# homeboard15.net
KiCad netlist of a schematic drawn in EAGLE
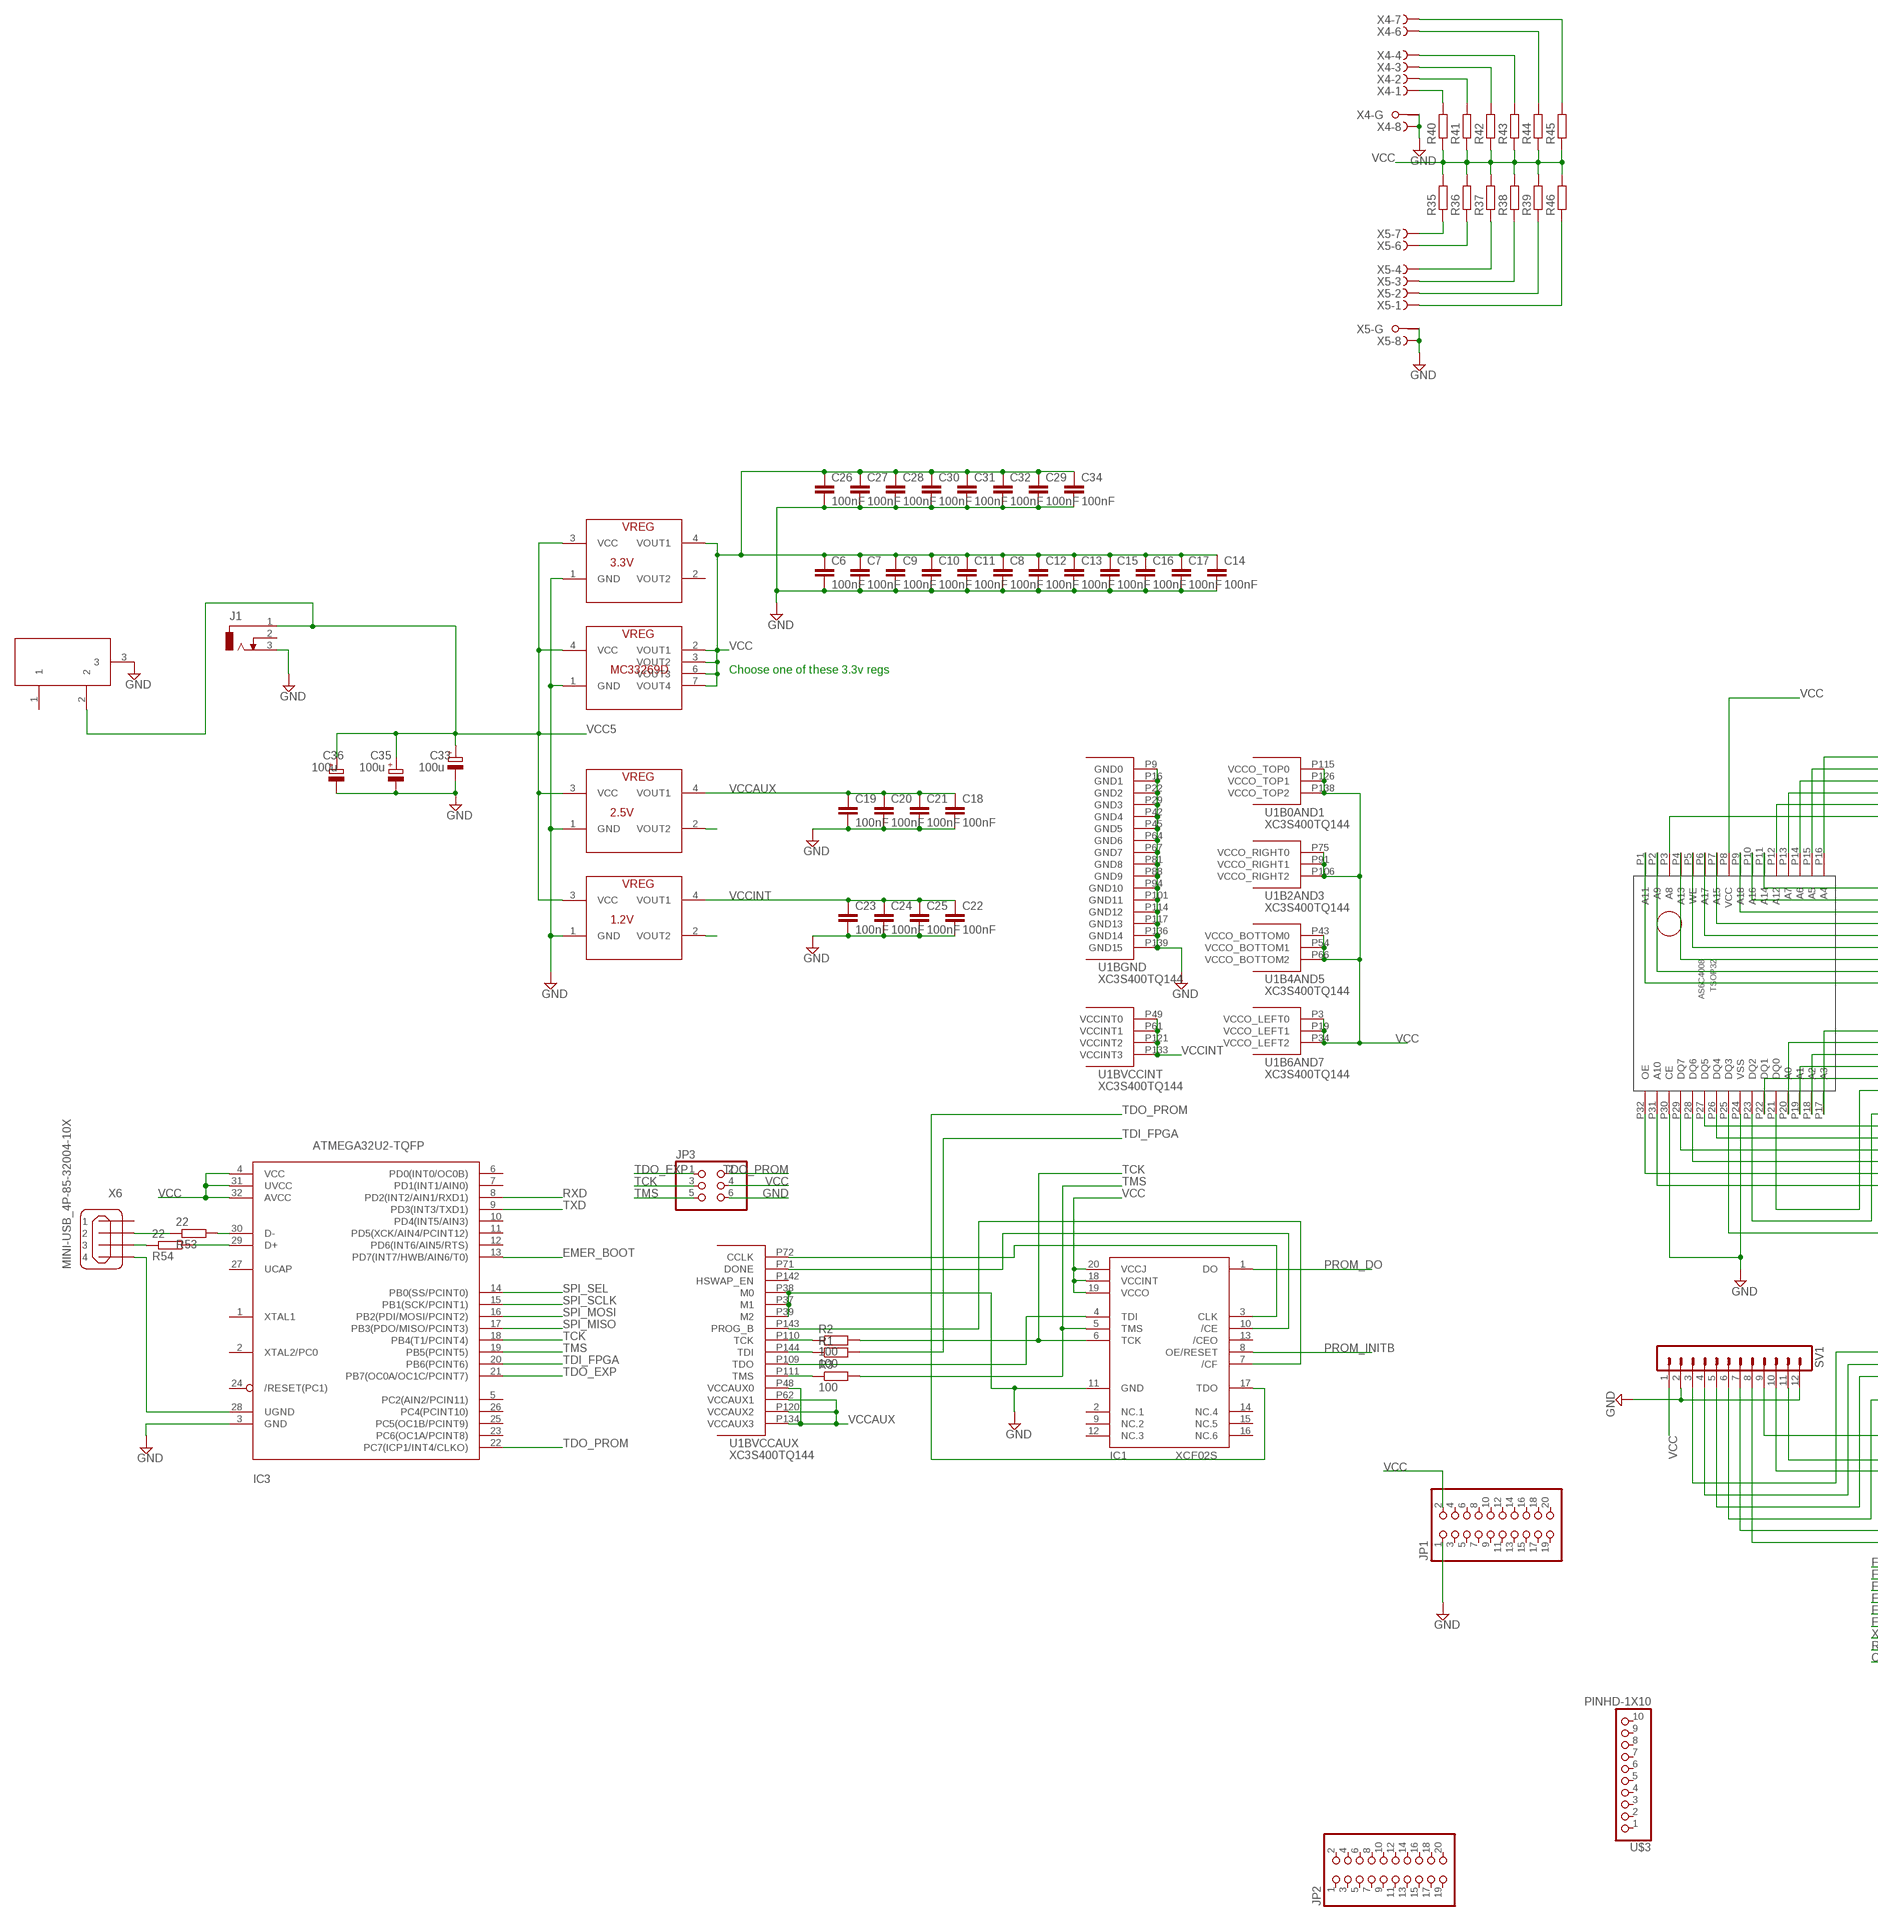
[diagram p0: schematic, sheet 1, part 1 of 3]
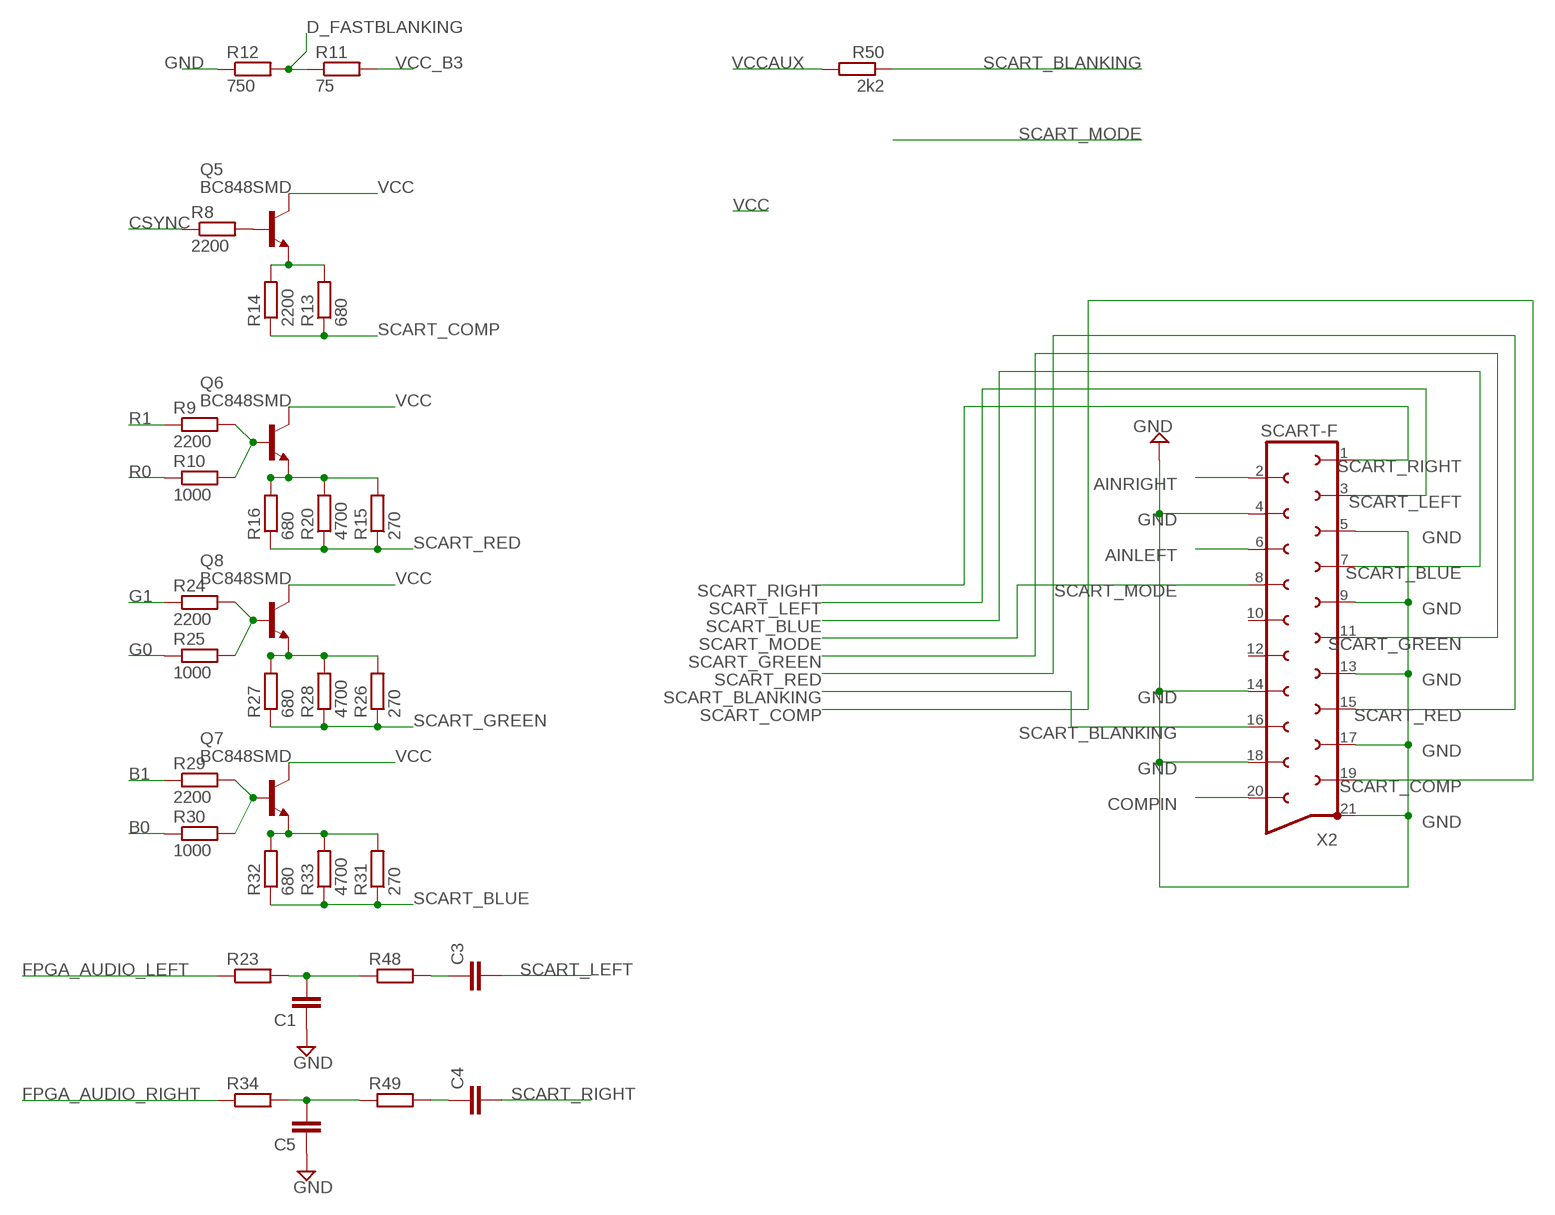
[diagram p1: schematic, sheet 1, part 2 of 3]
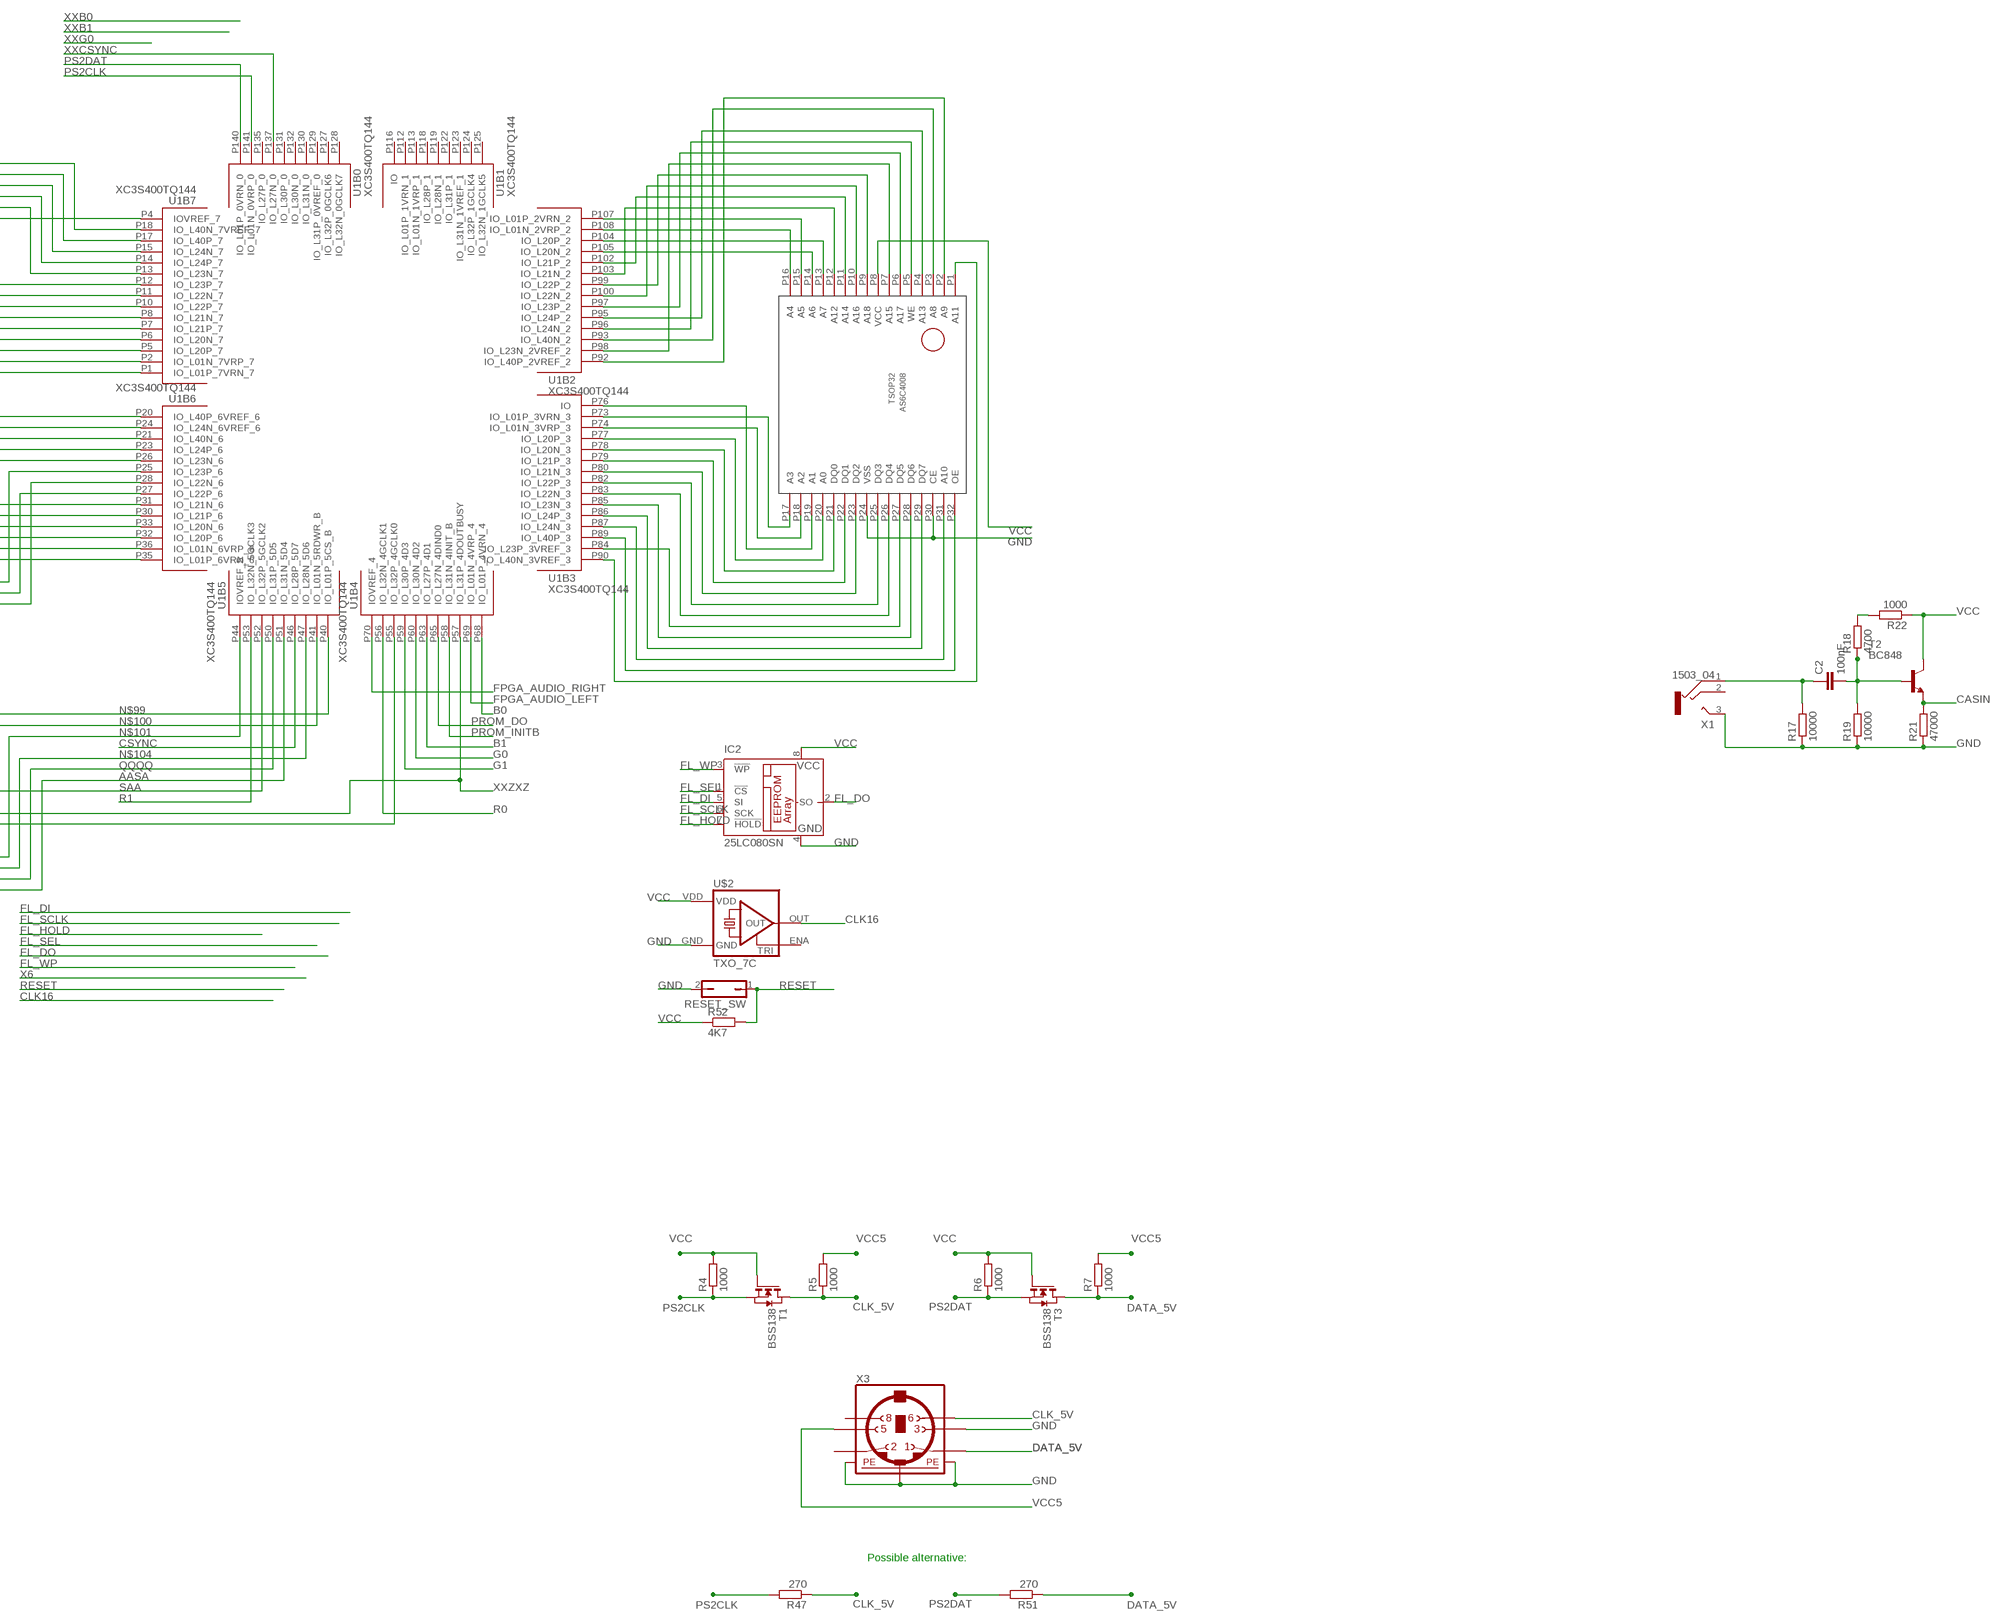
[diagram p2: schematic, sheet 1, part 3 of 3]

(export (version "E")
  (design (tool "Eeschema 10.0.6"))
  (components
    (comp (ref "C1")
      (value "C-EUC0603")
      (footprint "eagle-import:C0603")
      (libsource (lib "eagle-import") (part "resistor_C-EUC0603"))
    )
    (comp (ref "C2")
      (value "100nF")
      (footprint "eagle-import:C0603")
      (libsource (lib "eagle-import") (part "resistor_C-EUC0603"))
    )
    (comp (ref "C3")
      (value "C-EUC0603")
      (footprint "eagle-import:C0603")
      (libsource (lib "eagle-import") (part "resistor_C-EUC0603"))
    )
    (comp (ref "C4")
      (value "C-EUC0603")
      (footprint "eagle-import:C0603")
      (libsource (lib "eagle-import") (part "resistor_C-EUC0603"))
    )
    (comp (ref "C5")
      (value "C-EUC0603")
      (footprint "eagle-import:C0603")
      (libsource (lib "eagle-import") (part "resistor_C-EUC0603"))
    )
    (comp (ref "C6")
      (value "100nF")
      (footprint "eagle-import:C0603")
      (libsource (lib "eagle-import") (part "C-EUC0603"))
    )
    (comp (ref "C7")
      (value "100nF")
      (footprint "eagle-import:C0603")
      (libsource (lib "eagle-import") (part "C-EUC0603"))
    )
    (comp (ref "C8")
      (value "100nF")
      (footprint "eagle-import:C0603")
      (libsource (lib "eagle-import") (part "C-EUC0603"))
    )
    (comp (ref "C9")
      (value "100nF")
      (footprint "eagle-import:C0603")
      (libsource (lib "eagle-import") (part "C-EUC0603"))
    )
    (comp (ref "C10")
      (value "100nF")
      (footprint "eagle-import:C0603")
      (libsource (lib "eagle-import") (part "C-EUC0603"))
    )
    (comp (ref "C11")
      (value "100nF")
      (footprint "eagle-import:C0603")
      (libsource (lib "eagle-import") (part "C-EUC0603"))
    )
    (comp (ref "C12")
      (value "100nF")
      (footprint "eagle-import:C0603")
      (libsource (lib "eagle-import") (part "C-EUC0603"))
    )
    (comp (ref "C13")
      (value "100nF")
      (footprint "eagle-import:C0603")
      (libsource (lib "eagle-import") (part "C-EUC0603"))
    )
    (comp (ref "C14")
      (value "100nF")
      (footprint "eagle-import:C0603")
      (libsource (lib "eagle-import") (part "C-EUC0603"))
    )
    (comp (ref "C15")
      (value "100nF")
      (footprint "eagle-import:C0603")
      (libsource (lib "eagle-import") (part "C-EUC0603"))
    )
    (comp (ref "C16")
      (value "100nF")
      (footprint "eagle-import:C0603")
      (libsource (lib "eagle-import") (part "C-EUC0603"))
    )
    (comp (ref "C17")
      (value "100nF")
      (footprint "eagle-import:C0603")
      (libsource (lib "eagle-import") (part "C-EUC0603"))
    )
    (comp (ref "C18")
      (value "100nF")
      (footprint "eagle-import:C0603")
      (libsource (lib "eagle-import") (part "C-EUC0603"))
    )
    (comp (ref "C19")
      (value "100nF")
      (footprint "eagle-import:C0603")
      (libsource (lib "eagle-import") (part "C-EUC0603"))
    )
    (comp (ref "C20")
      (value "100nF")
      (footprint "eagle-import:C0603")
      (libsource (lib "eagle-import") (part "C-EUC0603"))
    )
    (comp (ref "C21")
      (value "100nF")
      (footprint "eagle-import:C0603")
      (libsource (lib "eagle-import") (part "C-EUC0603"))
    )
    (comp (ref "C22")
      (value "100nF")
      (footprint "eagle-import:C0603")
      (libsource (lib "eagle-import") (part "C-EUC0603"))
    )
    (comp (ref "C23")
      (value "100nF")
      (footprint "eagle-import:C0603")
      (libsource (lib "eagle-import") (part "C-EUC0603"))
    )
    (comp (ref "C24")
      (value "100nF")
      (footprint "eagle-import:C0603")
      (libsource (lib "eagle-import") (part "C-EUC0603"))
    )
    (comp (ref "C25")
      (value "100nF")
      (footprint "eagle-import:C0603")
      (libsource (lib "eagle-import") (part "C-EUC0603"))
    )
    (comp (ref "C26")
      (value "100nF")
      (footprint "eagle-import:C0603")
      (libsource (lib "eagle-import") (part "C-EUC0603"))
    )
    (comp (ref "C27")
      (value "100nF")
      (footprint "eagle-import:C0603")
      (libsource (lib "eagle-import") (part "C-EUC0603"))
    )
    (comp (ref "C28")
      (value "100nF")
      (footprint "eagle-import:C0603")
      (libsource (lib "eagle-import") (part "C-EUC0603"))
    )
    (comp (ref "C29")
      (value "100nF")
      (footprint "eagle-import:C0603")
      (libsource (lib "eagle-import") (part "C-EUC0603"))
    )
    (comp (ref "C30")
      (value "100nF")
      (footprint "eagle-import:C0603")
      (libsource (lib "eagle-import") (part "C-EUC0603"))
    )
    (comp (ref "C31")
      (value "100nF")
      (footprint "eagle-import:C0603")
      (libsource (lib "eagle-import") (part "C-EUC0603"))
    )
    (comp (ref "C32")
      (value "100nF")
      (footprint "eagle-import:C0603")
      (libsource (lib "eagle-import") (part "C-EUC0603"))
    )
    (comp (ref "C33")
      (value "100u")
      (footprint "eagle-import:PANASONIC_D")
      (libsource (lib "eagle-import") (part "CPOL-EUD"))
    )
    (comp (ref "C34")
      (value "100nF")
      (footprint "eagle-import:C0603")
      (libsource (lib "eagle-import") (part "C-EUC0603"))
    )
    (comp (ref "C35")
      (value "100u")
      (footprint "eagle-import:PANASONIC_D")
      (libsource (lib "eagle-import") (part "CPOL-EUD"))
    )
    (comp (ref "C36")
      (value "100u")
      (footprint "eagle-import:PANASONIC_D")
      (libsource (lib "eagle-import") (part "CPOL-EUD"))
    )
    (comp (ref "IC1")
      (value "XCF02S")
      (footprint "eagle-import:VO20")
      (libsource (lib "eagle-import") (part "XCF02S"))
    )
    (comp (ref "IC2")
      (value "25LC080SN")
      (footprint "eagle-import:SO-08")
      (fields (field (name "MF") "MICROCHIP") (field (name "MPN") "25LC080/SN"))
      (libsource (lib "eagle-import") (part "25SNLC080"))
    )
    (comp (ref "IC3")
      (value "ATMEGA32U2-TQFP")
      (footprint "eagle-import:TQFP32-08")
      (libsource (lib "eagle-import") (part "ATMEGA32U2-TQFP"))
    )
    (comp (ref "J1")
      (value "DCJ0303")
      (footprint "eagle-import:DCJ0303")
      (libsource (lib "eagle-import") (part "DCJ0303"))
    )
    (comp (ref "JP1")
      (value "PINHD-2X10")
      (footprint "eagle-import:2X10")
      (libsource (lib "eagle-import") (part "PINHD-2X10"))
    )
    (comp (ref "JP2")
      (value "PINHD-2X10")
      (footprint "eagle-import:2X10")
      (libsource (lib "eagle-import") (part "PINHD-2X10"))
    )
    (comp (ref "JP3")
      (value "PINHD-2X3")
      (footprint "eagle-import:2X03")
      (libsource (lib "eagle-import") (part "PINHD-2X3"))
    )
    (comp (ref "Q5")
      (value "BC848SMD")
      (footprint "eagle-import:SOT23")
      (libsource (lib "eagle-import") (part "BC848SMD"))
    )
    (comp (ref "Q6")
      (value "BC848SMD")
      (footprint "eagle-import:SOT23")
      (libsource (lib "eagle-import") (part "BC848SMD"))
    )
    (comp (ref "Q7")
      (value "BC848SMD")
      (footprint "eagle-import:SOT23")
      (libsource (lib "eagle-import") (part "BC848SMD"))
    )
    (comp (ref "Q8")
      (value "BC848SMD")
      (footprint "eagle-import:SOT23")
      (libsource (lib "eagle-import") (part "BC848SMD"))
    )
    (comp (ref "R1")
      (value "100")
      (footprint "eagle-import:R0805")
      (libsource (lib "eagle-import") (part "R-EU_R0805"))
    )
    (comp (ref "R2")
      (value "100")
      (footprint "eagle-import:R0805")
      (libsource (lib "eagle-import") (part "R-EU_R0805"))
    )
    (comp (ref "R3")
      (value "100")
      (footprint "eagle-import:R0805")
      (libsource (lib "eagle-import") (part "R-EU_R0805"))
    )
    (comp (ref "R4")
      (value "1000")
      (footprint "eagle-import:R0805")
      (libsource (lib "eagle-import") (part "R-EU_R0805"))
    )
    (comp (ref "R5")
      (value "1000")
      (footprint "eagle-import:R0805")
      (libsource (lib "eagle-import") (part "R-EU_R0805"))
    )
    (comp (ref "R6")
      (value "1000")
      (footprint "eagle-import:R0805")
      (libsource (lib "eagle-import") (part "R-EU_R0805"))
    )
    (comp (ref "R7")
      (value "1000")
      (footprint "eagle-import:R0805")
      (libsource (lib "eagle-import") (part "R-EU_R0805"))
    )
    (comp (ref "R8")
      (value "2200")
      (footprint "eagle-import:R0805")
      (libsource (lib "eagle-import") (part "R-EU_R0805"))
    )
    (comp (ref "R9")
      (value "2200")
      (footprint "eagle-import:R0805")
      (libsource (lib "eagle-import") (part "R-EU_R0805"))
    )
    (comp (ref "R10")
      (value "1000")
      (footprint "eagle-import:R0805")
      (libsource (lib "eagle-import") (part "R-EU_R0805"))
    )
    (comp (ref "R11")
      (value "75")
      (footprint "eagle-import:R0805")
      (libsource (lib "eagle-import") (part "R-EU_R0805"))
    )
    (comp (ref "R12")
      (value "750")
      (footprint "eagle-import:R0805")
      (libsource (lib "eagle-import") (part "R-EU_R0805"))
    )
    (comp (ref "R13")
      (value "680")
      (footprint "eagle-import:R0805")
      (libsource (lib "eagle-import") (part "R-EU_R0805"))
    )
    (comp (ref "R14")
      (value "2200")
      (footprint "eagle-import:R0805")
      (libsource (lib "eagle-import") (part "R-EU_R0805"))
    )
    (comp (ref "R15")
      (value "270")
      (footprint "eagle-import:R0805")
      (libsource (lib "eagle-import") (part "R-EU_R0805"))
    )
    (comp (ref "R16")
      (value "680")
      (footprint "eagle-import:R0805")
      (libsource (lib "eagle-import") (part "R-EU_R0805"))
    )
    (comp (ref "R17")
      (value "10000")
      (footprint "eagle-import:R0805")
      (libsource (lib "eagle-import") (part "R-EU_R0805"))
    )
    (comp (ref "R18")
      (value "4700")
      (footprint "eagle-import:R0805")
      (libsource (lib "eagle-import") (part "R-EU_R0805"))
    )
    (comp (ref "R19")
      (value "10000")
      (footprint "eagle-import:R0805")
      (libsource (lib "eagle-import") (part "R-EU_R0805"))
    )
    (comp (ref "R20")
      (value "4700")
      (footprint "eagle-import:R0805")
      (libsource (lib "eagle-import") (part "R-EU_R0805"))
    )
    (comp (ref "R21")
      (value "47000")
      (footprint "eagle-import:R0805")
      (libsource (lib "eagle-import") (part "R-EU_R0805"))
    )
    (comp (ref "R22")
      (value "1000")
      (footprint "eagle-import:R0805")
      (libsource (lib "eagle-import") (part "R-EU_R0805"))
    )
    (comp (ref "R23")
      (value "R-EU_M0805")
      (footprint "eagle-import:M0805")
      (libsource (lib "eagle-import") (part "resistor_R-EU_M0805"))
    )
    (comp (ref "R24")
      (value "2200")
      (footprint "eagle-import:R0805")
      (libsource (lib "eagle-import") (part "R-EU_R0805"))
    )
    (comp (ref "R25")
      (value "1000")
      (footprint "eagle-import:R0805")
      (libsource (lib "eagle-import") (part "R-EU_R0805"))
    )
    (comp (ref "R26")
      (value "270")
      (footprint "eagle-import:R0805")
      (libsource (lib "eagle-import") (part "R-EU_R0805"))
    )
    (comp (ref "R27")
      (value "680")
      (footprint "eagle-import:R0805")
      (libsource (lib "eagle-import") (part "R-EU_R0805"))
    )
    (comp (ref "R28")
      (value "4700")
      (footprint "eagle-import:R0805")
      (libsource (lib "eagle-import") (part "R-EU_R0805"))
    )
    (comp (ref "R29")
      (value "2200")
      (footprint "eagle-import:R0805")
      (libsource (lib "eagle-import") (part "R-EU_R0805"))
    )
    (comp (ref "R30")
      (value "1000")
      (footprint "eagle-import:R0805")
      (libsource (lib "eagle-import") (part "R-EU_R0805"))
    )
    (comp (ref "R31")
      (value "270")
      (footprint "eagle-import:R0805")
      (libsource (lib "eagle-import") (part "R-EU_R0805"))
    )
    (comp (ref "R32")
      (value "680")
      (footprint "eagle-import:R0805")
      (libsource (lib "eagle-import") (part "R-EU_R0805"))
    )
    (comp (ref "R33")
      (value "4700")
      (footprint "eagle-import:R0805")
      (libsource (lib "eagle-import") (part "R-EU_R0805"))
    )
    (comp (ref "R34")
      (value "R-EU_M0805")
      (footprint "eagle-import:M0805")
      (libsource (lib "eagle-import") (part "resistor_R-EU_M0805"))
    )
    (comp (ref "R35")
      (value "R-EU_M0805")
      (footprint "eagle-import:M0805")
      (libsource (lib "eagle-import") (part "resistor_R-EU_M0805"))
    )
    (comp (ref "R36")
      (value "R-EU_M0805")
      (footprint "eagle-import:M0805")
      (libsource (lib "eagle-import") (part "resistor_R-EU_M0805"))
    )
    (comp (ref "R37")
      (value "R-EU_M0805")
      (footprint "eagle-import:M0805")
      (libsource (lib "eagle-import") (part "resistor_R-EU_M0805"))
    )
    (comp (ref "R38")
      (value "R-EU_M0805")
      (footprint "eagle-import:M0805")
      (libsource (lib "eagle-import") (part "resistor_R-EU_M0805"))
    )
    (comp (ref "R39")
      (value "R-EU_M0805")
      (footprint "eagle-import:M0805")
      (libsource (lib "eagle-import") (part "resistor_R-EU_M0805"))
    )
    (comp (ref "R40")
      (value "R-EU_M0805")
      (footprint "eagle-import:M0805")
      (libsource (lib "eagle-import") (part "resistor_R-EU_M0805"))
    )
    (comp (ref "R41")
      (value "R-EU_M0805")
      (footprint "eagle-import:M0805")
      (libsource (lib "eagle-import") (part "resistor_R-EU_M0805"))
    )
    (comp (ref "R42")
      (value "R-EU_M0805")
      (footprint "eagle-import:M0805")
      (libsource (lib "eagle-import") (part "resistor_R-EU_M0805"))
    )
    (comp (ref "R43")
      (value "R-EU_M0805")
      (footprint "eagle-import:M0805")
      (libsource (lib "eagle-import") (part "resistor_R-EU_M0805"))
    )
    (comp (ref "R44")
      (value "R-EU_M0805")
      (footprint "eagle-import:M0805")
      (libsource (lib "eagle-import") (part "resistor_R-EU_M0805"))
    )
    (comp (ref "R45")
      (value "R-EU_M0805")
      (footprint "eagle-import:M0805")
      (libsource (lib "eagle-import") (part "resistor_R-EU_M0805"))
    )
    (comp (ref "R46")
      (value "R-EU_M0805")
      (footprint "eagle-import:M0805")
      (libsource (lib "eagle-import") (part "resistor_R-EU_M0805"))
    )
    (comp (ref "R47")
      (value "270")
      (footprint "eagle-import:R0805")
      (libsource (lib "eagle-import") (part "R-EU_R0805"))
    )
    (comp (ref "R48")
      (value "R-EU_M0805")
      (footprint "eagle-import:M0805")
      (libsource (lib "eagle-import") (part "resistor_R-EU_M0805"))
    )
    (comp (ref "R49")
      (value "R-EU_M0805")
      (footprint "eagle-import:M0805")
      (libsource (lib "eagle-import") (part "resistor_R-EU_M0805"))
    )
    (comp (ref "R50")
      (value "2k2")
      (footprint "eagle-import:M0805")
      (libsource (lib "eagle-import") (part "resistor_R-EU_M0805"))
    )
    (comp (ref "R51")
      (value "270")
      (footprint "eagle-import:R0805")
      (libsource (lib "eagle-import") (part "R-EU_R0805"))
    )
    (comp (ref "R52")
      (value "4K7")
      (footprint "eagle-import:M0805")
      (libsource (lib "eagle-import") (part "resistor_R-EU_M0805"))
    )
    (comp (ref "R53")
      (value "22")
      (footprint "eagle-import:R0805")
      (libsource (lib "eagle-import") (part "R-EU_R0805"))
    )
    (comp (ref "R54")
      (value "22")
      (footprint "eagle-import:R0805")
      (libsource (lib "eagle-import") (part "R-EU_R0805"))
    )
    (comp (ref "REG1.2")
      (value "1.2V")
      (footprint "eagle-import:SOT223")
      (libsource (lib "eagle-import") (part "NX1117"))
    )
    (comp (ref "REG2.5")
      (value "2.5V")
      (footprint "eagle-import:SOT223")
      (libsource (lib "eagle-import") (part "NX1117"))
    )
    (comp (ref "RESET_SW")
      (value "JP1Q")
      (footprint "eagle-import:JP1")
      (libsource (lib "eagle-import") (part "JP1Q"))
    )
    (comp (ref "SV1")
      (value "MA12-1")
      (footprint "eagle-import:MA12-1")
      (libsource (lib "eagle-import") (part "MA12-1"))
    )
    (comp (ref "T1")
      (value "BSS138")
      (footprint "eagle-import:SOT-23")
      (libsource (lib "eagle-import") (part "NMOSSOT23"))
    )
    (comp (ref "T2")
      (value "BC848")
      (footprint "eagle-import:SOT23")
      (libsource (lib "eagle-import") (part "BC848"))
    )
    (comp (ref "T3")
      (value "BSS138")
      (footprint "eagle-import:SOT-23")
      (libsource (lib "eagle-import") (part "NMOSSOT23"))
    )
    (comp (ref "U$1")
      (value "AS6C4008")
      (footprint "eagle-import:TSOP32")
      (libsource (lib "eagle-import") (part "AS6C4008"))
    )
    (comp (ref "U$2")
      (value "TXO_7C")
      (footprint "eagle-import:OSC_7C")
      (libsource (lib "eagle-import") (part "TXO_7C"))
    )
    (comp (ref "U$3")
      (value "PINHD-1X10")
      (footprint "eagle-import:1X10-BIG")
      (libsource (lib "eagle-import") (part "PINHD-1X10"))
    )
    (comp (ref "U$4")
      (value "3.3V")
      (footprint "eagle-import:SOT223")
      (libsource (lib "eagle-import") (part "NX1117"))
    )
    (comp (ref "U$5")
      (value "MC33269D")
      (footprint "eagle-import:SO8")
      (libsource (lib "eagle-import") (part "MC33269D"))
    )
    (comp (ref "U$6")
      (value "AS6C4008")
      (footprint "eagle-import:TSOP32")
      (libsource (lib "eagle-import") (part "AS6C4008"))
    )
    (comp (ref "U1")
      (value "XC3S400TQ144")
      (footprint "eagle-import:TQ144")
      (libsource (lib "eagle-import") (part "XC3S400TQ144"))
    )
    (comp (ref "X1")
      (value "1503_04")
      (footprint "eagle-import:1503_04")
      (libsource (lib "eagle-import") (part "1503_04"))
    )
    (comp (ref "X2")
      (value "SCART-F")
      (footprint "eagle-import:SCART-F")
      (libsource (lib "eagle-import") (part "SCART-F"))
    )
    (comp (ref "X3")
      (value "MINI_DIN_6")
      (footprint "eagle-import:M_DIN6")
      (libsource (lib "eagle-import") (part "MINI_DIN_6"))
    )
    (comp (ref "X4")
      (value "F09HPS")
      (footprint "eagle-import:F09HP")
      (libsource (lib "eagle-import") (part "F09HPS"))
    )
    (comp (ref "X5")
      (value "F09HPS")
      (footprint "eagle-import:F09HP")
      (libsource (lib "eagle-import") (part "F09HPS"))
    )
    (comp (ref "X6")
      (value "MINI-USB_4P-85-32004-10X")
      (footprint "eagle-import:85-32004-10X")
      (libsource (lib "eagle-import") (part "MINI-USB_4P-85-32004-10X"))
    )
    (comp (ref "X7")
      (value "DC21MMX")
      (footprint "eagle-import:DC-21MM")
      (libsource (lib "eagle-import") (part "DC21MMX"))
    )
  )
  (nets
    (net (code "1") (name "/1") (class "Default")
      (node (ref "X7") (pin "1") (pinfunction "1_1") (pintype "power_in"))
    )
    (net (code "2") (name "/AASA") (class "Default")
      (node (ref "SV1") (pin "8") (pinfunction "8_8") (pintype "passive"))
      (node (ref "U1") (pin "P51") (pinfunction "IO_L31N_5D4_P51") (pintype "bidirectional"))
    )
    (net (code "3") (name "/AINLEFT") (class "Default")
      (node (ref "X2") (pin "6") (pinfunction "6_6") (pintype "passive"))
    )
    (net (code "4") (name "/AINRIGHT") (class "Default")
      (node (ref "X2") (pin "2") (pinfunction "2_2") (pintype "passive"))
    )
    (net (code "5") (name "/B0") (class "Default")
      (node (ref "R30") (pin "1") (pinfunction "1_1") (pintype "passive"))
      (node (ref "U1") (pin "P68") (pinfunction "IO_L01P_4VRN_4_P68") (pintype "bidirectional"))
    )
    (net (code "6") (name "/B1") (class "Default")
      (node (ref "R29") (pin "1") (pinfunction "1_1") (pintype "passive"))
      (node (ref "U1") (pin "P63") (pinfunction "IO_L27P_4D1_P63") (pintype "bidirectional"))
    )
    (net (code "7") (name "/CASIN") (class "Default")
      (node (ref "R21") (pin "2") (pinfunction "2_2") (pintype "passive"))
      (node (ref "T2") (pin "2") (pinfunction "E_2") (pintype "passive"))
    )
    (net (code "8") (name "/CLK16") (class "Default")
      (node (ref "U$2") (pin "OUT") (pinfunction "OUT_OUT") (pintype "output"))
    )
    (net (code "9") (name "/CLK_5V") (class "Default")
      (node (ref "R47") (pin "1") (pinfunction "1_1") (pintype "passive"))
      (node (ref "R5") (pin "1") (pinfunction "1_1") (pintype "passive"))
      (node (ref "T1") (pin "1") (pinfunction "D_1") (pintype "passive"))
      (node (ref "X3") (pin "6") (pinfunction "6_6") (pintype "passive"))
    )
    (net (code "10") (name "/COMPIN") (class "Default")
      (node (ref "X2") (pin "20") (pinfunction "20_20") (pintype "passive"))
    )
    (net (code "11") (name "/CSYNC") (class "Default")
      (node (ref "R8") (pin "1") (pinfunction "1_1") (pintype "passive"))
      (node (ref "U1") (pin "P46") (pinfunction "IO_L28P_5D7_P46") (pintype "bidirectional"))
    )
    (net (code "12") (name "/DATA_5V") (class "Default")
      (node (ref "R51") (pin "1") (pinfunction "1_1") (pintype "passive"))
      (node (ref "R7") (pin "1") (pinfunction "1_1") (pintype "passive"))
      (node (ref "T3") (pin "1") (pinfunction "D_1") (pintype "passive"))
      (node (ref "X3") (pin "1") (pinfunction "1_1") (pintype "passive"))
    )
    (net (code "13") (name "/D_FASTBLANKING") (class "Default")
      (node (ref "R11") (pin "1") (pinfunction "1_1") (pintype "passive"))
      (node (ref "R12") (pin "2") (pinfunction "2_2") (pintype "passive"))
    )
    (net (code "14") (name "/EMER_BOOT") (class "Default")
      (node (ref "IC3") (pin "13") (pinfunction "PD7(INT7/HWB/AIN6/T0)_13") (pintype "bidirectional"))
    )
    (net (code "15") (name "/FL_DI") (class "Default")
      (node (ref "IC2") (pin "5") (pinfunction "SI_5") (pintype "input"))
    )
    (net (code "16") (name "/FL_DO") (class "Default")
      (node (ref "IC2") (pin "2") (pinfunction "SO_2") (pintype "bidirectional"))
    )
    (net (code "17") (name "/FL_HOLD") (class "Default")
      (node (ref "IC2") (pin "7") (pinfunction "~{HOLD}_7") (pintype "input"))
    )
    (net (code "18") (name "/FL_SCLK") (class "Default")
      (node (ref "IC2") (pin "6") (pinfunction "SCK_6") (pintype "input"))
    )
    (net (code "19") (name "/FL_SEL") (class "Default")
      (node (ref "IC2") (pin "1") (pinfunction "~{CS}_1") (pintype "input"))
    )
    (net (code "20") (name "/FL_WP") (class "Default")
      (node (ref "IC2") (pin "3") (pinfunction "~{WP}_3") (pintype "input"))
    )
    (net (code "21") (name "/FPGA_AUDIO_LEFT") (class "Default")
      (node (ref "R23") (pin "1") (pinfunction "1_1") (pintype "passive"))
      (node (ref "U1") (pin "P69") (pinfunction "IO_L01N_4VRP_4_P69") (pintype "bidirectional"))
    )
    (net (code "22") (name "/FPGA_AUDIO_RIGHT") (class "Default")
      (node (ref "R34") (pin "1") (pinfunction "1_1") (pintype "passive"))
      (node (ref "U1") (pin "P70") (pinfunction "IOVREF_4_P70") (pintype "bidirectional"))
    )
    (net (code "23") (name "/G0") (class "Default")
      (node (ref "R25") (pin "1") (pinfunction "1_1") (pintype "passive"))
      (node (ref "U1") (pin "P60") (pinfunction "IO_L30N_4D2_P60") (pintype "bidirectional"))
    )
    (net (code "24") (name "/G1") (class "Default")
      (node (ref "R24") (pin "1") (pinfunction "1_1") (pintype "passive"))
      (node (ref "U1") (pin "P59") (pinfunction "IO_L30P_4D3_P59") (pintype "bidirectional"))
    )
    (net (code "25") (name "/N$99") (class "Default")
      (node (ref "SV1") (pin "3") (pinfunction "3_3") (pintype "passive"))
      (node (ref "U1") (pin "P40") (pinfunction "IO_L01P_5CS_B_P40") (pintype "bidirectional"))
    )
    (net (code "26") (name "/N$100") (class "Default")
      (node (ref "SV1") (pin "4") (pinfunction "4_4") (pintype "passive"))
      (node (ref "U1") (pin "P41") (pinfunction "IO_L01N_5RDWR_B_P41") (pintype "bidirectional"))
    )
    (net (code "27") (name "/N$101") (class "Default")
      (node (ref "SV1") (pin "5") (pinfunction "5_5") (pintype "passive"))
      (node (ref "U1") (pin "P44") (pinfunction "IOVREF_5_P44") (pintype "bidirectional"))
    )
    (net (code "28") (name "/N$104") (class "Default")
      (node (ref "SV1") (pin "6") (pinfunction "6_6") (pintype "passive"))
      (node (ref "U1") (pin "P47") (pinfunction "IO_L28N_5D6_P47") (pintype "bidirectional"))
    )
    (net (code "29") (name "/PROM_DO") (class "Default")
      (node (ref "IC1") (pin "1") (pinfunction "DO_1") (pintype "bidirectional"))
      (node (ref "U1") (pin "P65") (pinfunction "IO_L27N_4DIND0_P65") (pintype "bidirectional"))
    )
    (net (code "30") (name "/PROM_INITB") (class "Default")
      (node (ref "IC1") (pin "8") (pinfunction "OE/RESET_8") (pintype "bidirectional"))
      (node (ref "U1") (pin "P58") (pinfunction "IO_L31N_4INIT_B_P58") (pintype "bidirectional"))
    )
    (net (code "31") (name "/PS2CLK") (class "Default")
      (node (ref "R4") (pin "1") (pinfunction "1_1") (pintype "passive"))
      (node (ref "R47") (pin "2") (pinfunction "2_2") (pintype "passive"))
      (node (ref "T1") (pin "2") (pinfunction "S_2") (pintype "passive"))
      (node (ref "U1") (pin "P141") (pinfunction "IO_L01N_0VRP_0_P141") (pintype "bidirectional"))
    )
    (net (code "32") (name "/PS2DAT") (class "Default")
      (node (ref "R51") (pin "2") (pinfunction "2_2") (pintype "passive"))
      (node (ref "R6") (pin "1") (pinfunction "1_1") (pintype "passive"))
      (node (ref "T3") (pin "2") (pinfunction "S_2") (pintype "passive"))
      (node (ref "U1") (pin "P140") (pinfunction "IO_L01P_0VRN_0_P140") (pintype "bidirectional"))
    )
    (net (code "33") (name "/QQQQ") (class "Default")
      (node (ref "SV1") (pin "7") (pinfunction "7_7") (pintype "passive"))
      (node (ref "U1") (pin "P50") (pinfunction "IO_L31P_5D5_P50") (pintype "bidirectional"))
    )
    (net (code "34") (name "/R0") (class "Default")
      (node (ref "R10") (pin "1") (pinfunction "1_1") (pintype "passive"))
      (node (ref "U1") (pin "P56") (pinfunction "IO_L32N_4GCLK1_P56") (pintype "bidirectional"))
    )
    (net (code "35") (name "/R1") (class "Default")
      (node (ref "R9") (pin "1") (pinfunction "1_1") (pintype "passive"))
      (node (ref "U1") (pin "P53") (pinfunction "IO_L32N_5GCLK3_P53") (pintype "bidirectional"))
    )
    (net (code "36") (name "/RESET") (class "Default")
      (node (ref "R52") (pin "2") (pinfunction "2_2") (pintype "passive"))
      (node (ref "RESET_SW") (pin "1") (pinfunction "1_1") (pintype "passive"))
    )
    (net (code "37") (name "/RXD") (class "Default")
      (node (ref "IC3") (pin "8") (pinfunction "PD2(INT2/AIN1/RXD1)_8") (pintype "bidirectional"))
    )
    (net (code "38") (name "/SAA") (class "Default")
      (node (ref "SV1") (pin "9") (pinfunction "9_9") (pintype "passive"))
      (node (ref "U1") (pin "P52") (pinfunction "IO_L32P_5GCLK2_P52") (pintype "bidirectional"))
    )
    (net (code "39") (name "/SCART_BLANKING") (class "Default")
      (node (ref "R50") (pin "1") (pinfunction "1_1") (pintype "passive"))
      (node (ref "X2") (pin "16") (pinfunction "16_16") (pintype "passive"))
    )
    (net (code "40") (name "/SCART_BLUE") (class "Default")
      (node (ref "R31") (pin "1") (pinfunction "1_1") (pintype "passive"))
      (node (ref "R32") (pin "1") (pinfunction "1_1") (pintype "passive"))
      (node (ref "R33") (pin "1") (pinfunction "1_1") (pintype "passive"))
      (node (ref "X2") (pin "7") (pinfunction "7_7") (pintype "passive"))
    )
    (net (code "41") (name "/SCART_COMP") (class "Default")
      (node (ref "R13") (pin "1") (pinfunction "1_1") (pintype "passive"))
      (node (ref "R14") (pin "1") (pinfunction "1_1") (pintype "passive"))
      (node (ref "X2") (pin "19") (pinfunction "19_19") (pintype "passive"))
    )
    (net (code "42") (name "/SCART_GREEN") (class "Default")
      (node (ref "R26") (pin "1") (pinfunction "1_1") (pintype "passive"))
      (node (ref "R27") (pin "1") (pinfunction "1_1") (pintype "passive"))
      (node (ref "R28") (pin "1") (pinfunction "1_1") (pintype "passive"))
      (node (ref "X2") (pin "11") (pinfunction "11_11") (pintype "passive"))
    )
    (net (code "43") (name "/SCART_LEFT") (class "Default")
      (node (ref "C3") (pin "2") (pinfunction "2_2") (pintype "passive"))
      (node (ref "X2") (pin "3") (pinfunction "3_3") (pintype "passive"))
    )
    (net (code "44") (name "/SCART_MODE") (class "Default")
      (node (ref "X2") (pin "8") (pinfunction "8_8") (pintype "passive"))
    )
    (net (code "45") (name "/SCART_RED") (class "Default")
      (node (ref "R15") (pin "1") (pinfunction "1_1") (pintype "passive"))
      (node (ref "R16") (pin "1") (pinfunction "1_1") (pintype "passive"))
      (node (ref "R20") (pin "1") (pinfunction "1_1") (pintype "passive"))
      (node (ref "X2") (pin "15") (pinfunction "15_15") (pintype "passive"))
    )
    (net (code "46") (name "/SCART_RIGHT") (class "Default")
      (node (ref "C4") (pin "2") (pinfunction "2_2") (pintype "passive"))
      (node (ref "X2") (pin "1") (pinfunction "1_1") (pintype "passive"))
    )
    (net (code "47") (name "/SPI_MISO") (class "Default")
      (node (ref "IC3") (pin "17") (pinfunction "PB3(PDO/MISO/PCINT3)_17") (pintype "bidirectional"))
    )
    (net (code "48") (name "/SPI_MOSI") (class "Default")
      (node (ref "IC3") (pin "16") (pinfunction "PB2(PDI/MOSI/PCINT2)_16") (pintype "bidirectional"))
    )
    (net (code "49") (name "/SPI_SCLK") (class "Default")
      (node (ref "IC3") (pin "15") (pinfunction "PB1(SCK/PCINT1)_15") (pintype "bidirectional"))
    )
    (net (code "50") (name "/SPI_SEL") (class "Default")
      (node (ref "IC3") (pin "14") (pinfunction "PB0(SS/PCINT0)_14") (pintype "bidirectional"))
    )
    (net (code "51") (name "/TCK") (class "Default")
      (node (ref "IC1") (pin "6") (pinfunction "TCK_6") (pintype "bidirectional"))
      (node (ref "IC3") (pin "18") (pinfunction "PB4(T1/PCINT4)_18") (pintype "bidirectional"))
      (node (ref "JP3") (pin "3") (pinfunction "3_3") (pintype "passive"))
      (node (ref "R2") (pin "2") (pinfunction "2_2") (pintype "passive"))
    )
    (net (code "52") (name "/TDI_FPGA") (class "Default")
      (node (ref "IC3") (pin "20") (pinfunction "PB6(PCINT6)_20") (pintype "bidirectional"))
      (node (ref "R1") (pin "2") (pinfunction "2_2") (pintype "passive"))
    )
    (net (code "53") (name "/TDO_EXP") (class "Default")
      (node (ref "IC3") (pin "21") (pinfunction "PB7(OC0A/OC1C/PCINT7)_21") (pintype "bidirectional"))
      (node (ref "JP3") (pin "1") (pinfunction "1_1") (pintype "passive"))
    )
    (net (code "54") (name "/TDO_PROM") (class "Default")
      (node (ref "IC1") (pin "17") (pinfunction "TDO_17") (pintype "bidirectional"))
      (node (ref "IC3") (pin "22") (pinfunction "PC7(ICP1/INT4/CLKO)_22") (pintype "bidirectional"))
      (node (ref "JP3") (pin "2") (pinfunction "2_2") (pintype "passive"))
    )
    (net (code "55") (name "/TMS") (class "Default")
      (node (ref "IC1") (pin "5") (pinfunction "TMS_5") (pintype "bidirectional"))
      (node (ref "IC3") (pin "19") (pinfunction "PB5(PCINT5)_19") (pintype "bidirectional"))
      (node (ref "JP3") (pin "5") (pinfunction "5_5") (pintype "passive"))
      (node (ref "R3") (pin "2") (pinfunction "2_2") (pintype "passive"))
    )
    (net (code "56") (name "/TXD") (class "Default")
      (node (ref "IC3") (pin "9") (pinfunction "PD3(INT3/TXD1)_9") (pintype "bidirectional"))
    )
    (net (code "57") (name "/VCC") (class "Default")
      (node (ref "C10") (pin "1") (pinfunction "1_1") (pintype "passive"))
      (node (ref "C11") (pin "1") (pinfunction "1_1") (pintype "passive"))
      (node (ref "C12") (pin "1") (pinfunction "1_1") (pintype "passive"))
      (node (ref "C13") (pin "1") (pinfunction "1_1") (pintype "passive"))
      (node (ref "C14") (pin "1") (pinfunction "1_1") (pintype "passive"))
      (node (ref "C15") (pin "1") (pinfunction "1_1") (pintype "passive"))
      (node (ref "C16") (pin "1") (pinfunction "1_1") (pintype "passive"))
      (node (ref "C17") (pin "1") (pinfunction "1_1") (pintype "passive"))
      (node (ref "C26") (pin "1") (pinfunction "1_1") (pintype "passive"))
      (node (ref "C27") (pin "1") (pinfunction "1_1") (pintype "passive"))
      (node (ref "C28") (pin "1") (pinfunction "1_1") (pintype "passive"))
      (node (ref "C29") (pin "1") (pinfunction "1_1") (pintype "passive"))
      (node (ref "C30") (pin "1") (pinfunction "1_1") (pintype "passive"))
      (node (ref "C31") (pin "1") (pinfunction "1_1") (pintype "passive"))
      (node (ref "C32") (pin "1") (pinfunction "1_1") (pintype "passive"))
      (node (ref "C34") (pin "1") (pinfunction "1_1") (pintype "passive"))
      (node (ref "C6") (pin "1") (pinfunction "1_1") (pintype "passive"))
      (node (ref "C7") (pin "1") (pinfunction "1_1") (pintype "passive"))
      (node (ref "C8") (pin "1") (pinfunction "1_1") (pintype "passive"))
      (node (ref "C9") (pin "1") (pinfunction "1_1") (pintype "passive"))
      (node (ref "IC1") (pin "18") (pinfunction "VCCINT_18") (pintype "bidirectional"))
      (node (ref "IC1") (pin "19") (pinfunction "VCCO_19") (pintype "bidirectional"))
      (node (ref "IC1") (pin "20") (pinfunction "VCCJ_20") (pintype "bidirectional"))
      (node (ref "IC2") (pin "8") (pinfunction "VCC_8") (pintype "power_in"))
      (node (ref "IC3") (pin "31") (pinfunction "UVCC_31") (pintype "bidirectional"))
      (node (ref "IC3") (pin "32") (pinfunction "AVCC_32") (pintype "bidirectional"))
      (node (ref "IC3") (pin "4") (pinfunction "VCC_4") (pintype "bidirectional"))
      (node (ref "JP1") (pin "2") (pinfunction "2_2") (pintype "passive"))
      (node (ref "JP3") (pin "4") (pinfunction "4_4") (pintype "passive"))
      (node (ref "Q5") (pin "3") (pinfunction "C_3") (pintype "passive"))
      (node (ref "Q6") (pin "3") (pinfunction "C_3") (pintype "passive"))
      (node (ref "Q7") (pin "3") (pinfunction "C_3") (pintype "passive"))
      (node (ref "Q8") (pin "3") (pinfunction "C_3") (pintype "passive"))
      (node (ref "R22") (pin "1") (pinfunction "1_1") (pintype "passive"))
      (node (ref "R35") (pin "2") (pinfunction "2_2") (pintype "passive"))
      (node (ref "R36") (pin "2") (pinfunction "2_2") (pintype "passive"))
      (node (ref "R37") (pin "2") (pinfunction "2_2") (pintype "passive"))
      (node (ref "R38") (pin "2") (pinfunction "2_2") (pintype "passive"))
      (node (ref "R39") (pin "2") (pinfunction "2_2") (pintype "passive"))
      (node (ref "R4") (pin "2") (pinfunction "2_2") (pintype "passive"))
      (node (ref "R40") (pin "1") (pinfunction "1_1") (pintype "passive"))
      (node (ref "R41") (pin "1") (pinfunction "1_1") (pintype "passive"))
      (node (ref "R42") (pin "1") (pinfunction "1_1") (pintype "passive"))
      (node (ref "R43") (pin "1") (pinfunction "1_1") (pintype "passive"))
      (node (ref "R44") (pin "1") (pinfunction "1_1") (pintype "passive"))
      (node (ref "R45") (pin "1") (pinfunction "1_1") (pintype "passive"))
      (node (ref "R46") (pin "2") (pinfunction "2_2") (pintype "passive"))
      (node (ref "R52") (pin "1") (pinfunction "1_1") (pintype "passive"))
      (node (ref "R6") (pin "2") (pinfunction "2_2") (pintype "passive"))
      (node (ref "SV1") (pin "1") (pinfunction "1_1") (pintype "passive"))
      (node (ref "T1") (pin "3") (pinfunction "G_3") (pintype "passive"))
      (node (ref "T2") (pin "3") (pinfunction "C_3") (pintype "passive"))
      (node (ref "T3") (pin "3") (pinfunction "G_3") (pintype "passive"))
      (node (ref "U$1") (pin "P8") (pinfunction "VCC_P8") (pintype "bidirectional"))
      (node (ref "U$2") (pin "VDD") (pinfunction "VDD_VDD") (pintype "power_in"))
      (node (ref "U$4") (pin "4") (pinfunction "VOUT1_4") (pintype "bidirectional"))
      (node (ref "U$5") (pin "2") (pinfunction "VOUT1_2") (pintype "output"))
      (node (ref "U$5") (pin "3") (pinfunction "VOUT2_3") (pintype "output"))
      (node (ref "U$5") (pin "6") (pinfunction "VOUT3_6") (pintype "output"))
      (node (ref "U$5") (pin "7") (pinfunction "VOUT4_7") (pintype "output"))
      (node (ref "U$6") (pin "P8") (pinfunction "VCC_P8") (pintype "bidirectional"))
      (node (ref "U1") (pin "P106") (pinfunction "VCCO_RIGHT2_P106") (pintype "passive"))
      (node (ref "U1") (pin "P115") (pinfunction "VCCO_TOP0_P115") (pintype "passive"))
      (node (ref "U1") (pin "P126") (pinfunction "VCCO_TOP1_P126") (pintype "passive"))
      (node (ref "U1") (pin "P138") (pinfunction "VCCO_TOP2_P138") (pintype "passive"))
      (node (ref "U1") (pin "P19") (pinfunction "VCCO_LEFT1_P19") (pintype "passive"))
      (node (ref "U1") (pin "P3") (pinfunction "VCCO_LEFT0_P3") (pintype "passive"))
      (node (ref "U1") (pin "P34") (pinfunction "VCCO_LEFT2_P34") (pintype "passive"))
      (node (ref "U1") (pin "P43") (pinfunction "VCCO_BOTTOM0_P43") (pintype "passive"))
      (node (ref "U1") (pin "P54") (pinfunction "VCCO_BOTTOM1_P54") (pintype "passive"))
      (node (ref "U1") (pin "P66") (pinfunction "VCCO_BOTTOM2_P66") (pintype "passive"))
      (node (ref "U1") (pin "P75") (pinfunction "VCCO_RIGHT0_P75") (pintype "passive"))
      (node (ref "U1") (pin "P91") (pinfunction "VCCO_RIGHT1_P91") (pintype "passive"))
    )
    (net (code "58") (name "/VCC5") (class "Default")
      (node (ref "C33") (pin "+") (pinfunction "+_+") (pintype "passive"))
      (node (ref "C35") (pin "+") (pinfunction "+_+") (pintype "passive"))
      (node (ref "C36") (pin "+") (pinfunction "+_+") (pintype "passive"))
      (node (ref "J1") (pin "1") (pinfunction "1_1") (pintype "passive"))
      (node (ref "R5") (pin "2") (pinfunction "2_2") (pintype "passive"))
      (node (ref "R7") (pin "2") (pinfunction "2_2") (pintype "passive"))
      (node (ref "REG1.2") (pin "3") (pinfunction "VCC_3") (pintype "bidirectional"))
      (node (ref "REG2.5") (pin "3") (pinfunction "VCC_3") (pintype "bidirectional"))
      (node (ref "U$4") (pin "3") (pinfunction "VCC_3") (pintype "bidirectional"))
      (node (ref "U$5") (pin "4") (pinfunction "VCC_4") (pintype "bidirectional"))
      (node (ref "X3") (pin "5") (pinfunction "5_5") (pintype "passive"))
      (node (ref "X7") (pin "2") (pinfunction "2_2") (pintype "power_in"))
    )
    (net (code "59") (name "/VCCAUX") (class "Default")
      (node (ref "C18") (pin "1") (pinfunction "1_1") (pintype "passive"))
      (node (ref "C19") (pin "1") (pinfunction "1_1") (pintype "passive"))
      (node (ref "C20") (pin "1") (pinfunction "1_1") (pintype "passive"))
      (node (ref "C21") (pin "1") (pinfunction "1_1") (pintype "passive"))
      (node (ref "R50") (pin "2") (pinfunction "2_2") (pintype "passive"))
      (node (ref "REG2.5") (pin "4") (pinfunction "VOUT1_4") (pintype "bidirectional"))
      (node (ref "U1") (pin "P120") (pinfunction "VCCAUX2_P120") (pintype "passive"))
      (node (ref "U1") (pin "P134") (pinfunction "VCCAUX3_P134") (pintype "passive"))
      (node (ref "U1") (pin "P48") (pinfunction "VCCAUX0_P48") (pintype "passive"))
      (node (ref "U1") (pin "P62") (pinfunction "VCCAUX1_P62") (pintype "passive"))
    )
    (net (code "60") (name "/VCCINT") (class "Default")
      (node (ref "C22") (pin "1") (pinfunction "1_1") (pintype "passive"))
      (node (ref "C23") (pin "1") (pinfunction "1_1") (pintype "passive"))
      (node (ref "C24") (pin "1") (pinfunction "1_1") (pintype "passive"))
      (node (ref "C25") (pin "1") (pinfunction "1_1") (pintype "passive"))
      (node (ref "REG1.2") (pin "4") (pinfunction "VOUT1_4") (pintype "bidirectional"))
      (node (ref "U1") (pin "P121") (pinfunction "VCCINT2_P121") (pintype "passive"))
      (node (ref "U1") (pin "P133") (pinfunction "VCCINT3_P133") (pintype "passive"))
      (node (ref "U1") (pin "P49") (pinfunction "VCCINT0_P49") (pintype "passive"))
      (node (ref "U1") (pin "P61") (pinfunction "VCCINT1_P61") (pintype "passive"))
    )
    (net (code "61") (name "/VCC_B3") (class "Default")
      (node (ref "R11") (pin "2") (pinfunction "2_2") (pintype "passive"))
    )
    (net (code "65") (name "/XXCSYNC") (class "Default")
      (node (ref "U1") (pin "P137") (pinfunction "IO_L27N_0_P137") (pintype "bidirectional"))
    )
    (net (code "67") (name "/XXZXZ") (class "Default")
      (node (ref "SV1") (pin "11") (pinfunction "11_11") (pintype "passive"))
      (node (ref "U1") (pin "P57") (pinfunction "IO_L31P_4DOUTBUSY_P57") (pintype "bidirectional"))
    )
    (net (code "68") (name "GND") (class "Default")
      (node (ref "C1") (pin "1") (pinfunction "1_1") (pintype "passive"))
      (node (ref "C10") (pin "2") (pinfunction "2_2") (pintype "passive"))
      (node (ref "C11") (pin "2") (pinfunction "2_2") (pintype "passive"))
      (node (ref "C12") (pin "2") (pinfunction "2_2") (pintype "passive"))
      (node (ref "C13") (pin "2") (pinfunction "2_2") (pintype "passive"))
      (node (ref "C14") (pin "2") (pinfunction "2_2") (pintype "passive"))
      (node (ref "C15") (pin "2") (pinfunction "2_2") (pintype "passive"))
      (node (ref "C16") (pin "2") (pinfunction "2_2") (pintype "passive"))
      (node (ref "C17") (pin "2") (pinfunction "2_2") (pintype "passive"))
      (node (ref "C18") (pin "2") (pinfunction "2_2") (pintype "passive"))
      (node (ref "C19") (pin "2") (pinfunction "2_2") (pintype "passive"))
      (node (ref "C20") (pin "2") (pinfunction "2_2") (pintype "passive"))
      (node (ref "C21") (pin "2") (pinfunction "2_2") (pintype "passive"))
      (node (ref "C22") (pin "2") (pinfunction "2_2") (pintype "passive"))
      (node (ref "C23") (pin "2") (pinfunction "2_2") (pintype "passive"))
      (node (ref "C24") (pin "2") (pinfunction "2_2") (pintype "passive"))
      (node (ref "C25") (pin "2") (pinfunction "2_2") (pintype "passive"))
      (node (ref "C26") (pin "2") (pinfunction "2_2") (pintype "passive"))
      (node (ref "C27") (pin "2") (pinfunction "2_2") (pintype "passive"))
      (node (ref "C28") (pin "2") (pinfunction "2_2") (pintype "passive"))
      (node (ref "C29") (pin "2") (pinfunction "2_2") (pintype "passive"))
      (node (ref "C30") (pin "2") (pinfunction "2_2") (pintype "passive"))
      (node (ref "C31") (pin "2") (pinfunction "2_2") (pintype "passive"))
      (node (ref "C32") (pin "2") (pinfunction "2_2") (pintype "passive"))
      (node (ref "C33") (pin "-") (pinfunction "-_-") (pintype "passive"))
      (node (ref "C34") (pin "2") (pinfunction "2_2") (pintype "passive"))
      (node (ref "C35") (pin "-") (pinfunction "-_-") (pintype "passive"))
      (node (ref "C36") (pin "-") (pinfunction "-_-") (pintype "passive"))
      (node (ref "C5") (pin "1") (pinfunction "1_1") (pintype "passive"))
      (node (ref "C6") (pin "2") (pinfunction "2_2") (pintype "passive"))
      (node (ref "C7") (pin "2") (pinfunction "2_2") (pintype "passive"))
      (node (ref "C8") (pin "2") (pinfunction "2_2") (pintype "passive"))
      (node (ref "C9") (pin "2") (pinfunction "2_2") (pintype "passive"))
      (node (ref "IC1") (pin "11") (pinfunction "GND_11") (pintype "bidirectional"))
      (node (ref "IC2") (pin "4") (pinfunction "GND_4") (pintype "power_in"))
      (node (ref "IC3") (pin "3") (pinfunction "GND_3") (pintype "bidirectional"))
      (node (ref "J1") (pin "3") (pinfunction "3_3") (pintype "passive"))
      (node (ref "JP1") (pin "1") (pinfunction "1_1") (pintype "passive"))
      (node (ref "JP3") (pin "6") (pinfunction "6_6") (pintype "passive"))
      (node (ref "R12") (pin "1") (pinfunction "1_1") (pintype "passive"))
      (node (ref "R17") (pin "1") (pinfunction "1_1") (pintype "passive"))
      (node (ref "R19") (pin "1") (pinfunction "1_1") (pintype "passive"))
      (node (ref "R21") (pin "1") (pinfunction "1_1") (pintype "passive"))
      (node (ref "REG1.2") (pin "1") (pinfunction "GND_1") (pintype "bidirectional"))
      (node (ref "REG2.5") (pin "1") (pinfunction "GND_1") (pintype "bidirectional"))
      (node (ref "RESET_SW") (pin "2") (pinfunction "2_2") (pintype "passive"))
      (node (ref "SV1") (pin "12") (pinfunction "12_12") (pintype "passive"))
      (node (ref "SV1") (pin "2") (pinfunction "2_2") (pintype "passive"))
      (node (ref "U$1") (pin "P24") (pinfunction "VSS_P24") (pintype "bidirectional"))
      (node (ref "U$1") (pin "P30") (pinfunction "CE_P30") (pintype "bidirectional"))
      (node (ref "U$2") (pin "GND") (pinfunction "GND_GND") (pintype "power_in"))
      (node (ref "U$4") (pin "1") (pinfunction "GND_1") (pintype "bidirectional"))
      (node (ref "U$5") (pin "1") (pinfunction "GND_1") (pintype "bidirectional"))
      (node (ref "U$6") (pin "P24") (pinfunction "VSS_P24") (pintype "bidirectional"))
      (node (ref "U$6") (pin "P30") (pinfunction "CE_P30") (pintype "bidirectional"))
      (node (ref "U1") (pin "P101") (pinfunction "GND11_P101") (pintype "passive"))
      (node (ref "U1") (pin "P114") (pinfunction "GND12_P114") (pintype "passive"))
      (node (ref "U1") (pin "P117") (pinfunction "GND13_P117") (pintype "passive"))
      (node (ref "U1") (pin "P136") (pinfunction "GND14_P136") (pintype "passive"))
      (node (ref "U1") (pin "P139") (pinfunction "GND15_P139") (pintype "passive"))
      (node (ref "U1") (pin "P16") (pinfunction "GND1_P16") (pintype "passive"))
      (node (ref "U1") (pin "P22") (pinfunction "GND2_P22") (pintype "passive"))
      (node (ref "U1") (pin "P29") (pinfunction "GND3_P29") (pintype "passive"))
      (node (ref "U1") (pin "P37") (pinfunction "M1_P37") (pintype "bidirectional"))
      (node (ref "U1") (pin "P38") (pinfunction "M0_P38") (pintype "bidirectional"))
      (node (ref "U1") (pin "P39") (pinfunction "M2_P39") (pintype "bidirectional"))
      (node (ref "U1") (pin "P42") (pinfunction "GND4_P42") (pintype "passive"))
      (node (ref "U1") (pin "P45") (pinfunction "GND5_P45") (pintype "passive"))
      (node (ref "U1") (pin "P64") (pinfunction "GND6_P64") (pintype "passive"))
      (node (ref "U1") (pin "P67") (pinfunction "GND7_P67") (pintype "passive"))
      (node (ref "U1") (pin "P81") (pinfunction "GND8_P81") (pintype "passive"))
      (node (ref "U1") (pin "P88") (pinfunction "GND9_P88") (pintype "passive"))
      (node (ref "U1") (pin "P9") (pinfunction "GND0_P9") (pintype "passive"))
      (node (ref "U1") (pin "P94") (pinfunction "GND10_P94") (pintype "passive"))
      (node (ref "X1") (pin "3") (pinfunction "2_3") (pintype "passive"))
      (node (ref "X2") (pin "13") (pinfunction "13_13") (pintype "passive"))
      (node (ref "X2") (pin "14") (pinfunction "14_14") (pintype "passive"))
      (node (ref "X2") (pin "17") (pinfunction "17_17") (pintype "passive"))
      (node (ref "X2") (pin "18") (pinfunction "18_18") (pintype "passive"))
      (node (ref "X2") (pin "21") (pinfunction "21_21") (pintype "passive"))
      (node (ref "X2") (pin "4") (pinfunction "4_4") (pintype "passive"))
      (node (ref "X2") (pin "5") (pinfunction "5_5") (pintype "passive"))
      (node (ref "X2") (pin "9") (pinfunction "9_9") (pintype "passive"))
      (node (ref "X3") (pin "3") (pinfunction "3_3") (pintype "passive"))
      (node (ref "X3") (pin "SH1") (pinfunction "PE1_SH1") (pintype "power_in"))
      (node (ref "X3") (pin "SH2") (pinfunction "PE2_SH2") (pintype "power_in"))
      (node (ref "X3") (pin "SH3") (pinfunction "PE3_SH3") (pintype "power_in"))
      (node (ref "X4") (pin "8") (pinfunction "F_8") (pintype "passive"))
      (node (ref "X4") (pin "G1") (pinfunction "G1_G1") (pintype "passive"))
      (node (ref "X5") (pin "8") (pinfunction "F_8") (pintype "passive"))
      (node (ref "X5") (pin "G1") (pinfunction "G1_G1") (pintype "passive"))
      (node (ref "X7") (pin "3") (pinfunction "3_3") (pintype "power_in"))
    )
    (net (code "69") (name "Net-(C1-Pad2)") (class "Default")
      (node (ref "C1") (pin "2") (pinfunction "2_2") (pintype "passive"))
      (node (ref "R23") (pin "2") (pinfunction "2_2") (pintype "passive"))
      (node (ref "R48") (pin "1") (pinfunction "1_1") (pintype "passive"))
    )
    (net (code "70") (name "Net-(C2-Pad1)") (class "Default")
      (node (ref "C2") (pin "1") (pinfunction "1_1") (pintype "passive"))
      (node (ref "R17") (pin "2") (pinfunction "2_2") (pintype "passive"))
      (node (ref "X1") (pin "1") (pinfunction "1_1") (pintype "passive"))
    )
    (net (code "71") (name "Net-(C3-Pad1)") (class "Default")
      (node (ref "C3") (pin "1") (pinfunction "1_1") (pintype "passive"))
      (node (ref "R48") (pin "2") (pinfunction "2_2") (pintype "passive"))
    )
    (net (code "72") (name "Net-(C4-Pad1)") (class "Default")
      (node (ref "C4") (pin "1") (pinfunction "1_1") (pintype "passive"))
      (node (ref "R49") (pin "2") (pinfunction "2_2") (pintype "passive"))
    )
    (net (code "73") (name "Net-(C5-Pad2)") (class "Default")
      (node (ref "C5") (pin "2") (pinfunction "2_2") (pintype "passive"))
      (node (ref "R34") (pin "2") (pinfunction "2_2") (pintype "passive"))
      (node (ref "R49") (pin "1") (pinfunction "1_1") (pintype "passive"))
    )
    (net (code "74") (name "Net-(IC1-CLK)") (class "Default")
      (node (ref "IC1") (pin "3") (pinfunction "CLK_3") (pintype "bidirectional"))
      (node (ref "U1") (pin "P72") (pinfunction "CCLK_P72") (pintype "bidirectional"))
    )
    (net (code "75") (name "Net-(IC1-TDI)") (class "Default")
      (node (ref "IC1") (pin "4") (pinfunction "TDI_4") (pintype "bidirectional"))
      (node (ref "U1") (pin "P109") (pinfunction "TDO_P109") (pintype "bidirectional"))
    )
    (net (code "76") (name "Net-(IC1-{slash}CE)") (class "Default")
      (node (ref "IC1") (pin "10") (pinfunction "/CE_10") (pintype "bidirectional"))
      (node (ref "U1") (pin "P71") (pinfunction "DONE_P71") (pintype "bidirectional"))
    )
    (net (code "77") (name "Net-(IC1-{slash}CF)") (class "Default")
      (node (ref "IC1") (pin "7") (pinfunction "/CF_7") (pintype "bidirectional"))
      (node (ref "U1") (pin "P143") (pinfunction "PROG_B_P143") (pintype "bidirectional"))
    )
    (net (code "78") (name "Net-(IC3-D+)") (class "Default")
      (node (ref "IC3") (pin "29") (pinfunction "D+_29") (pintype "bidirectional"))
      (node (ref "R54") (pin "2") (pinfunction "2_2") (pintype "passive"))
    )
    (net (code "79") (name "Net-(IC3-D-)") (class "Default")
      (node (ref "IC3") (pin "30") (pinfunction "D-_30") (pintype "bidirectional"))
      (node (ref "R53") (pin "2") (pinfunction "2_2") (pintype "passive"))
    )
    (net (code "80") (name "Net-(IC3-UGND)") (class "Default")
      (node (ref "IC3") (pin "28") (pinfunction "UGND_28") (pintype "bidirectional"))
      (node (ref "X6") (pin "4") (pinfunction "4_4") (pintype "passive"))
    )
    (net (code "81") (name "Net-(Q5-B)") (class "Default")
      (node (ref "Q5") (pin "1") (pinfunction "B_1") (pintype "passive"))
      (node (ref "R8") (pin "2") (pinfunction "2_2") (pintype "passive"))
    )
    (net (code "82") (name "Net-(Q5-E)") (class "Default")
      (node (ref "Q5") (pin "2") (pinfunction "E_2") (pintype "passive"))
      (node (ref "R13") (pin "2") (pinfunction "2_2") (pintype "passive"))
      (node (ref "R14") (pin "2") (pinfunction "2_2") (pintype "passive"))
    )
    (net (code "83") (name "Net-(Q6-B)") (class "Default")
      (node (ref "Q6") (pin "1") (pinfunction "B_1") (pintype "passive"))
      (node (ref "R10") (pin "2") (pinfunction "2_2") (pintype "passive"))
      (node (ref "R9") (pin "2") (pinfunction "2_2") (pintype "passive"))
    )
    (net (code "84") (name "Net-(Q6-E)") (class "Default")
      (node (ref "Q6") (pin "2") (pinfunction "E_2") (pintype "passive"))
      (node (ref "R15") (pin "2") (pinfunction "2_2") (pintype "passive"))
      (node (ref "R16") (pin "2") (pinfunction "2_2") (pintype "passive"))
      (node (ref "R20") (pin "2") (pinfunction "2_2") (pintype "passive"))
    )
    (net (code "85") (name "Net-(Q7-B)") (class "Default")
      (node (ref "Q7") (pin "1") (pinfunction "B_1") (pintype "passive"))
      (node (ref "R29") (pin "2") (pinfunction "2_2") (pintype "passive"))
      (node (ref "R30") (pin "2") (pinfunction "2_2") (pintype "passive"))
    )
    (net (code "86") (name "Net-(Q7-E)") (class "Default")
      (node (ref "Q7") (pin "2") (pinfunction "E_2") (pintype "passive"))
      (node (ref "R31") (pin "2") (pinfunction "2_2") (pintype "passive"))
      (node (ref "R32") (pin "2") (pinfunction "2_2") (pintype "passive"))
      (node (ref "R33") (pin "2") (pinfunction "2_2") (pintype "passive"))
    )
    (net (code "87") (name "Net-(Q8-B)") (class "Default")
      (node (ref "Q8") (pin "1") (pinfunction "B_1") (pintype "passive"))
      (node (ref "R24") (pin "2") (pinfunction "2_2") (pintype "passive"))
      (node (ref "R25") (pin "2") (pinfunction "2_2") (pintype "passive"))
    )
    (net (code "88") (name "Net-(Q8-E)") (class "Default")
      (node (ref "Q8") (pin "2") (pinfunction "E_2") (pintype "passive"))
      (node (ref "R26") (pin "2") (pinfunction "2_2") (pintype "passive"))
      (node (ref "R27") (pin "2") (pinfunction "2_2") (pintype "passive"))
      (node (ref "R28") (pin "2") (pinfunction "2_2") (pintype "passive"))
    )
    (net (code "89") (name "Net-(R18-Pad2)") (class "Default")
      (node (ref "R18") (pin "2") (pinfunction "2_2") (pintype "passive"))
      (node (ref "R22") (pin "2") (pinfunction "2_2") (pintype "passive"))
    )
    (net (code "90") (name "Net-(R53-Pad1)") (class "Default")
      (node (ref "R53") (pin "1") (pinfunction "1_1") (pintype "passive"))
      (node (ref "X6") (pin "2") (pinfunction "2_2") (pintype "passive"))
    )
    (net (code "91") (name "Net-(R54-Pad1)") (class "Default")
      (node (ref "R54") (pin "1") (pinfunction "1_1") (pintype "passive"))
      (node (ref "X6") (pin "3") (pinfunction "3_3") (pintype "passive"))
    )
    (net (code "92") (name "Net-(T2-B)") (class "Default")
      (node (ref "C2") (pin "2") (pinfunction "2_2") (pintype "passive"))
      (node (ref "R18") (pin "1") (pinfunction "1_1") (pintype "passive"))
      (node (ref "R19") (pin "2") (pinfunction "2_2") (pintype "passive"))
      (node (ref "T2") (pin "1") (pinfunction "B_1") (pintype "passive"))
    )
    (net (code "93") (name "Net-(U$1-A0)") (class "Default")
      (node (ref "U$1") (pin "P20") (pinfunction "A0_P20") (pintype "bidirectional"))
      (node (ref "U1") (pin "P77") (pinfunction "IO_L20P_3_P77") (pintype "bidirectional"))
    )
    (net (code "94") (name "Net-(U$1-A1)") (class "Default")
      (node (ref "U$1") (pin "P19") (pinfunction "A1_P19") (pintype "bidirectional"))
      (node (ref "U1") (pin "P76") (pinfunction "IO_P76") (pintype "bidirectional"))
    )
    (net (code "95") (name "Net-(U$1-A2)") (class "Default")
      (node (ref "U$1") (pin "P18") (pinfunction "A2_P18") (pintype "bidirectional"))
      (node (ref "U1") (pin "P74") (pinfunction "IO_L01N_3VRP_3_P74") (pintype "bidirectional"))
    )
    (net (code "96") (name "Net-(U$1-A3)") (class "Default")
      (node (ref "U$1") (pin "P17") (pinfunction "A3_P17") (pintype "bidirectional"))
      (node (ref "U1") (pin "P73") (pinfunction "IO_L01P_3VRN_3_P73") (pintype "bidirectional"))
    )
    (net (code "97") (name "Net-(U$1-A4)") (class "Default")
      (node (ref "U$1") (pin "P16") (pinfunction "A4_P16") (pintype "bidirectional"))
      (node (ref "U1") (pin "P108") (pinfunction "IO_L01N_2VRP_2_P108") (pintype "bidirectional"))
    )
    (net (code "98") (name "Net-(U$1-A5)") (class "Default")
      (node (ref "U$1") (pin "P15") (pinfunction "A5_P15") (pintype "bidirectional"))
      (node (ref "U1") (pin "P107") (pinfunction "IO_L01P_2VRN_2_P107") (pintype "bidirectional"))
    )
    (net (code "99") (name "Net-(U$1-A6)") (class "Default")
      (node (ref "U$1") (pin "P14") (pinfunction "A6_P14") (pintype "bidirectional"))
      (node (ref "U1") (pin "P105") (pinfunction "IO_L20N_2_P105") (pintype "bidirectional"))
    )
    (net (code "100") (name "Net-(U$1-A7)") (class "Default")
      (node (ref "U$1") (pin "P13") (pinfunction "A7_P13") (pintype "bidirectional"))
      (node (ref "U1") (pin "P104") (pinfunction "IO_L20P_2_P104") (pintype "bidirectional"))
    )
    (net (code "101") (name "Net-(U$1-A8)") (class "Default")
      (node (ref "U$1") (pin "P3") (pinfunction "A8_P3") (pintype "bidirectional"))
      (node (ref "U1") (pin "P93") (pinfunction "IO_L40N_2_P93") (pintype "bidirectional"))
    )
    (net (code "102") (name "Net-(U$1-A9)") (class "Default")
      (node (ref "U$1") (pin "P2") (pinfunction "A9_P2") (pintype "bidirectional"))
      (node (ref "U1") (pin "P92") (pinfunction "IO_L40P_2VREF_2_P92") (pintype "bidirectional"))
    )
    (net (code "103") (name "Net-(U$1-A10)") (class "Default")
      (node (ref "U$1") (pin "P31") (pinfunction "A10_P31") (pintype "bidirectional"))
      (node (ref "U1") (pin "P87") (pinfunction "IO_L24N_3_P87") (pintype "bidirectional"))
    )
    (net (code "104") (name "Net-(U$1-A11)") (class "Default")
      (node (ref "U$1") (pin "P1") (pinfunction "A11_P1") (pintype "bidirectional"))
      (node (ref "U1") (pin "P90") (pinfunction "IO_L40N_3VREF_3_P90") (pintype "bidirectional"))
    )
    (net (code "105") (name "Net-(U$1-A12)") (class "Default")
      (node (ref "U$1") (pin "P12") (pinfunction "A12_P12") (pintype "bidirectional"))
      (node (ref "U1") (pin "P103") (pinfunction "IO_L21N_2_P103") (pintype "bidirectional"))
    )
    (net (code "106") (name "Net-(U$1-A13)") (class "Default")
      (node (ref "U$1") (pin "P4") (pinfunction "A13_P4") (pintype "bidirectional"))
      (node (ref "U1") (pin "P95") (pinfunction "IO_L24P_2_P95") (pintype "bidirectional"))
    )
    (net (code "107") (name "Net-(U$1-A14)") (class "Default")
      (node (ref "U$1") (pin "P11") (pinfunction "A14_P11") (pintype "bidirectional"))
      (node (ref "U1") (pin "P102") (pinfunction "IO_L21P_2_P102") (pintype "bidirectional"))
    )
    (net (code "108") (name "Net-(U$1-A15)") (class "Default")
      (node (ref "U$1") (pin "P7") (pinfunction "A15_P7") (pintype "bidirectional"))
      (node (ref "U1") (pin "P98") (pinfunction "IO_L23N_2VREF_2_P98") (pintype "bidirectional"))
    )
    (net (code "109") (name "Net-(U$1-A16)") (class "Default")
      (node (ref "U$1") (pin "P10") (pinfunction "A16_P10") (pintype "bidirectional"))
      (node (ref "U1") (pin "P100") (pinfunction "IO_L22N_2_P100") (pintype "bidirectional"))
    )
    (net (code "110") (name "Net-(U$1-A17)") (class "Default")
      (node (ref "U$1") (pin "P6") (pinfunction "A17_P6") (pintype "bidirectional"))
      (node (ref "U1") (pin "P97") (pinfunction "IO_L23P_2_P97") (pintype "bidirectional"))
    )
    (net (code "111") (name "Net-(U$1-A18)") (class "Default")
      (node (ref "U$1") (pin "P9") (pinfunction "A18_P9") (pintype "bidirectional"))
      (node (ref "U1") (pin "P99") (pinfunction "IO_L22P_2_P99") (pintype "bidirectional"))
    )
    (net (code "112") (name "Net-(U$1-DQ0)") (class "Default")
      (node (ref "U$1") (pin "P21") (pinfunction "DQ0_P21") (pintype "bidirectional"))
      (node (ref "U1") (pin "P78") (pinfunction "IO_L20N_3_P78") (pintype "bidirectional"))
    )
    (net (code "113") (name "Net-(U$1-DQ1)") (class "Default")
      (node (ref "U$1") (pin "P22") (pinfunction "DQ1_P22") (pintype "bidirectional"))
      (node (ref "U1") (pin "P79") (pinfunction "IO_L21P_3_P79") (pintype "bidirectional"))
    )
    (net (code "114") (name "Net-(U$1-DQ2)") (class "Default")
      (node (ref "U$1") (pin "P23") (pinfunction "DQ2_P23") (pintype "bidirectional"))
      (node (ref "U1") (pin "P80") (pinfunction "IO_L21N_3_P80") (pintype "bidirectional"))
    )
    (net (code "115") (name "Net-(U$1-DQ3)") (class "Default")
      (node (ref "U$1") (pin "P25") (pinfunction "DQ3_P25") (pintype "bidirectional"))
      (node (ref "U1") (pin "P82") (pinfunction "IO_L22P_3_P82") (pintype "bidirectional"))
    )
    (net (code "116") (name "Net-(U$1-DQ4)") (class "Default")
      (node (ref "U$1") (pin "P26") (pinfunction "DQ4_P26") (pintype "bidirectional"))
      (node (ref "U1") (pin "P83") (pinfunction "IO_L22N_3_P83") (pintype "bidirectional"))
    )
    (net (code "117") (name "Net-(U$1-DQ5)") (class "Default")
      (node (ref "U$1") (pin "P27") (pinfunction "DQ5_P27") (pintype "bidirectional"))
      (node (ref "U1") (pin "P84") (pinfunction "IO_L23P_3VREF_3_P84") (pintype "bidirectional"))
    )
    (net (code "118") (name "Net-(U$1-DQ6)") (class "Default")
      (node (ref "U$1") (pin "P28") (pinfunction "DQ6_P28") (pintype "bidirectional"))
      (node (ref "U1") (pin "P85") (pinfunction "IO_L23N_3_P85") (pintype "bidirectional"))
    )
    (net (code "119") (name "Net-(U$1-DQ7)") (class "Default")
      (node (ref "U$1") (pin "P29") (pinfunction "DQ7_P29") (pintype "bidirectional"))
      (node (ref "U1") (pin "P86") (pinfunction "IO_L24P_3_P86") (pintype "bidirectional"))
    )
    (net (code "120") (name "Net-(U$1-OE)") (class "Default")
      (node (ref "U$1") (pin "P32") (pinfunction "OE_P32") (pintype "bidirectional"))
      (node (ref "U1") (pin "P89") (pinfunction "IO_L40P_3_P89") (pintype "bidirectional"))
    )
    (net (code "121") (name "Net-(U$1-WE)") (class "Default")
      (node (ref "U$1") (pin "P5") (pinfunction "WE_P5") (pintype "bidirectional"))
      (node (ref "U1") (pin "P96") (pinfunction "IO_L24N_2_P96") (pintype "bidirectional"))
    )
    (net (code "122") (name "Net-(U$6-A0)") (class "Default")
      (node (ref "U$6") (pin "P20") (pinfunction "A0_P20") (pintype "bidirectional"))
      (node (ref "U1") (pin "P24") (pinfunction "IO_L24N_6VREF_6_P24") (pintype "bidirectional"))
    )
    (net (code "123") (name "Net-(U$6-A1)") (class "Default")
      (node (ref "U$6") (pin "P19") (pinfunction "A1_P19") (pintype "bidirectional"))
      (node (ref "U1") (pin "P23") (pinfunction "IO_L24P_6_P23") (pintype "bidirectional"))
    )
    (net (code "124") (name "Net-(U$6-A2)") (class "Default")
      (node (ref "U$6") (pin "P18") (pinfunction "A2_P18") (pintype "bidirectional"))
      (node (ref "U1") (pin "P21") (pinfunction "IO_L40N_6_P21") (pintype "bidirectional"))
    )
    (net (code "125") (name "Net-(U$6-A3)") (class "Default")
      (node (ref "U$6") (pin "P17") (pinfunction "A3_P17") (pintype "bidirectional"))
      (node (ref "U1") (pin "P20") (pinfunction "IO_L40P_6VREF_6_P20") (pintype "bidirectional"))
    )
    (net (code "126") (name "Net-(U$6-A4)") (class "Default")
      (node (ref "U$6") (pin "P16") (pinfunction "A4_P16") (pintype "bidirectional"))
      (node (ref "U1") (pin "P18") (pinfunction "IO_L40N_7VREF_7_P18") (pintype "bidirectional"))
    )
    (net (code "127") (name "Net-(U$6-A5)") (class "Default")
      (node (ref "U$6") (pin "P15") (pinfunction "A5_P15") (pintype "bidirectional"))
      (node (ref "U1") (pin "P17") (pinfunction "IO_L40P_7_P17") (pintype "bidirectional"))
    )
    (net (code "128") (name "Net-(U$6-A6)") (class "Default")
      (node (ref "U$6") (pin "P14") (pinfunction "A6_P14") (pintype "bidirectional"))
      (node (ref "U1") (pin "P15") (pinfunction "IO_L24N_7_P15") (pintype "bidirectional"))
    )
    (net (code "129") (name "Net-(U$6-A7)") (class "Default")
      (node (ref "U$6") (pin "P13") (pinfunction "A7_P13") (pintype "bidirectional"))
      (node (ref "U1") (pin "P14") (pinfunction "IO_L24P_7_P14") (pintype "bidirectional"))
    )
    (net (code "130") (name "Net-(U$6-A8)") (class "Default")
      (node (ref "U$6") (pin "P3") (pinfunction "A8_P3") (pintype "bidirectional"))
      (node (ref "U1") (pin "P4") (pinfunction "IOVREF_7_P4") (pintype "bidirectional"))
    )
    (net (code "131") (name "Net-(U$6-A9)") (class "Default")
      (node (ref "U$6") (pin "P2") (pinfunction "A9_P2") (pintype "bidirectional"))
      (node (ref "U1") (pin "P2") (pinfunction "IO_L01N_7VRP_7_P2") (pintype "bidirectional"))
    )
    (net (code "132") (name "Net-(U$6-A10)") (class "Default")
      (node (ref "U$6") (pin "P31") (pinfunction "A10_P31") (pintype "bidirectional"))
      (node (ref "U1") (pin "P35") (pinfunction "IO_L01P_6VRN_6_P35") (pintype "bidirectional"))
    )
    (net (code "133") (name "Net-(U$6-A11)") (class "Default")
      (node (ref "U$6") (pin "P1") (pinfunction "A11_P1") (pintype "bidirectional"))
      (node (ref "U1") (pin "P1") (pinfunction "IO_L01P_7VRN_7_P1") (pintype "bidirectional"))
    )
    (net (code "134") (name "Net-(U$6-A12)") (class "Default")
      (node (ref "U$6") (pin "P12") (pinfunction "A12_P12") (pintype "bidirectional"))
      (node (ref "U1") (pin "P13") (pinfunction "IO_L23N_7_P13") (pintype "bidirectional"))
    )
    (net (code "135") (name "Net-(U$6-A13)") (class "Default")
      (node (ref "U$6") (pin "P4") (pinfunction "A13_P4") (pintype "bidirectional"))
      (node (ref "U1") (pin "P5") (pinfunction "IO_L20P_7_P5") (pintype "bidirectional"))
    )
    (net (code "136") (name "Net-(U$6-A14)") (class "Default")
      (node (ref "U$6") (pin "P11") (pinfunction "A14_P11") (pintype "bidirectional"))
      (node (ref "U1") (pin "P12") (pinfunction "IO_L23P_7_P12") (pintype "bidirectional"))
    )
    (net (code "137") (name "Net-(U$6-A15)") (class "Default")
      (node (ref "U$6") (pin "P7") (pinfunction "A15_P7") (pintype "bidirectional"))
      (node (ref "U1") (pin "P8") (pinfunction "IO_L21N_7_P8") (pintype "bidirectional"))
    )
    (net (code "138") (name "Net-(U$6-A16)") (class "Default")
      (node (ref "U$6") (pin "P10") (pinfunction "A16_P10") (pintype "bidirectional"))
      (node (ref "U1") (pin "P11") (pinfunction "IO_L22N_7_P11") (pintype "bidirectional"))
    )
    (net (code "139") (name "Net-(U$6-A17)") (class "Default")
      (node (ref "U$6") (pin "P6") (pinfunction "A17_P6") (pintype "bidirectional"))
      (node (ref "U1") (pin "P7") (pinfunction "IO_L21P_7_P7") (pintype "bidirectional"))
    )
    (net (code "140") (name "Net-(U$6-A18)") (class "Default")
      (node (ref "U$6") (pin "P9") (pinfunction "A18_P9") (pintype "bidirectional"))
      (node (ref "U1") (pin "P10") (pinfunction "IO_L22P_7_P10") (pintype "bidirectional"))
    )
    (net (code "141") (name "Net-(U$6-DQ0)") (class "Default")
      (node (ref "U$6") (pin "P21") (pinfunction "DQ0_P21") (pintype "bidirectional"))
      (node (ref "U1") (pin "P25") (pinfunction "IO_L23P_6_P25") (pintype "bidirectional"))
    )
    (net (code "142") (name "Net-(U$6-DQ1)") (class "Default")
      (node (ref "U$6") (pin "P22") (pinfunction "DQ1_P22") (pintype "bidirectional"))
      (node (ref "U1") (pin "P26") (pinfunction "IO_L23N_6_P26") (pintype "bidirectional"))
    )
    (net (code "143") (name "Net-(U$6-DQ2)") (class "Default")
      (node (ref "U$6") (pin "P23") (pinfunction "DQ2_P23") (pintype "bidirectional"))
      (node (ref "U1") (pin "P27") (pinfunction "IO_L22P_6_P27") (pintype "bidirectional"))
    )
    (net (code "144") (name "Net-(U$6-DQ3)") (class "Default")
      (node (ref "U$6") (pin "P25") (pinfunction "DQ3_P25") (pintype "bidirectional"))
      (node (ref "U1") (pin "P28") (pinfunction "IO_L22N_6_P28") (pintype "bidirectional"))
    )
    (net (code "145") (name "Net-(U$6-DQ4)") (class "Default")
      (node (ref "U$6") (pin "P26") (pinfunction "DQ4_P26") (pintype "bidirectional"))
      (node (ref "U1") (pin "P30") (pinfunction "IO_L21P_6_P30") (pintype "bidirectional"))
    )
    (net (code "146") (name "Net-(U$6-DQ5)") (class "Default")
      (node (ref "U$6") (pin "P27") (pinfunction "DQ5_P27") (pintype "bidirectional"))
      (node (ref "U1") (pin "P31") (pinfunction "IO_L21N_6_P31") (pintype "bidirectional"))
    )
    (net (code "147") (name "Net-(U$6-DQ6)") (class "Default")
      (node (ref "U$6") (pin "P28") (pinfunction "DQ6_P28") (pintype "bidirectional"))
      (node (ref "U1") (pin "P32") (pinfunction "IO_L20P_6_P32") (pintype "bidirectional"))
    )
    (net (code "148") (name "Net-(U$6-DQ7)") (class "Default")
      (node (ref "U$6") (pin "P29") (pinfunction "DQ7_P29") (pintype "bidirectional"))
      (node (ref "U1") (pin "P33") (pinfunction "IO_L20N_6_P33") (pintype "bidirectional"))
    )
    (net (code "149") (name "Net-(U$6-OE)") (class "Default")
      (node (ref "U$6") (pin "P32") (pinfunction "OE_P32") (pintype "bidirectional"))
      (node (ref "U1") (pin "P36") (pinfunction "IO_L01N_6VRP_6_P36") (pintype "bidirectional"))
    )
    (net (code "150") (name "Net-(U$6-WE)") (class "Default")
      (node (ref "U$6") (pin "P5") (pinfunction "WE_P5") (pintype "bidirectional"))
      (node (ref "U1") (pin "P6") (pinfunction "IO_L20N_7_P6") (pintype "bidirectional"))
    )
    (net (code "151") (name "Net-(U1G-IO_L32P_4GCLK0)") (class "Default")
      (node (ref "SV1") (pin "10") (pinfunction "10_10") (pintype "passive"))
      (node (ref "U1") (pin "P55") (pinfunction "IO_L32P_4GCLK0_P55") (pintype "bidirectional"))
    )
    (net (code "152") (name "Net-(U1N-TCK)") (class "Default")
      (node (ref "R2") (pin "1") (pinfunction "1_1") (pintype "passive"))
      (node (ref "U1") (pin "P110") (pinfunction "TCK_P110") (pintype "bidirectional"))
    )
    (net (code "153") (name "Net-(U1N-TDI)") (class "Default")
      (node (ref "R1") (pin "1") (pinfunction "1_1") (pintype "passive"))
      (node (ref "U1") (pin "P144") (pinfunction "TDI_P144") (pintype "bidirectional"))
    )
    (net (code "154") (name "Net-(U1N-TMS)") (class "Default")
      (node (ref "R3") (pin "1") (pinfunction "1_1") (pintype "passive"))
      (node (ref "U1") (pin "P111") (pinfunction "TMS_P111") (pintype "bidirectional"))
    )
    (net (code "155") (name "Net-(X4A-F)") (class "Default")
      (node (ref "R40") (pin "2") (pinfunction "2_2") (pintype "passive"))
      (node (ref "X4") (pin "1") (pinfunction "F_1") (pintype "passive"))
    )
    (net (code "156") (name "Net-(X4B-F)") (class "Default")
      (node (ref "R41") (pin "2") (pinfunction "2_2") (pintype "passive"))
      (node (ref "X4") (pin "2") (pinfunction "F_2") (pintype "passive"))
    )
    (net (code "157") (name "Net-(X4C-F)") (class "Default")
      (node (ref "R42") (pin "2") (pinfunction "2_2") (pintype "passive"))
      (node (ref "X4") (pin "3") (pinfunction "F_3") (pintype "passive"))
    )
    (net (code "158") (name "Net-(X4D-F)") (class "Default")
      (node (ref "R43") (pin "2") (pinfunction "2_2") (pintype "passive"))
      (node (ref "X4") (pin "4") (pinfunction "F_4") (pintype "passive"))
    )
    (net (code "159") (name "Net-(X4F-F)") (class "Default")
      (node (ref "R44") (pin "2") (pinfunction "2_2") (pintype "passive"))
      (node (ref "X4") (pin "6") (pinfunction "F_6") (pintype "passive"))
    )
    (net (code "160") (name "Net-(X4G-F)") (class "Default")
      (node (ref "R45") (pin "2") (pinfunction "2_2") (pintype "passive"))
      (node (ref "X4") (pin "7") (pinfunction "F_7") (pintype "passive"))
    )
    (net (code "161") (name "Net-(X5A-F)") (class "Default")
      (node (ref "R46") (pin "1") (pinfunction "1_1") (pintype "passive"))
      (node (ref "X5") (pin "1") (pinfunction "F_1") (pintype "passive"))
    )
    (net (code "162") (name "Net-(X5B-F)") (class "Default")
      (node (ref "R39") (pin "1") (pinfunction "1_1") (pintype "passive"))
      (node (ref "X5") (pin "2") (pinfunction "F_2") (pintype "passive"))
    )
    (net (code "163") (name "Net-(X5C-F)") (class "Default")
      (node (ref "R38") (pin "1") (pinfunction "1_1") (pintype "passive"))
      (node (ref "X5") (pin "3") (pinfunction "F_3") (pintype "passive"))
    )
    (net (code "164") (name "Net-(X5D-F)") (class "Default")
      (node (ref "R37") (pin "1") (pinfunction "1_1") (pintype "passive"))
      (node (ref "X5") (pin "4") (pinfunction "F_4") (pintype "passive"))
    )
    (net (code "165") (name "Net-(X5F-F)") (class "Default")
      (node (ref "R36") (pin "1") (pinfunction "1_1") (pintype "passive"))
      (node (ref "X5") (pin "6") (pinfunction "F_6") (pintype "passive"))
    )
    (net (code "166") (name "Net-(X5G-F)") (class "Default")
      (node (ref "R35") (pin "1") (pinfunction "1_1") (pintype "passive"))
      (node (ref "X5") (pin "7") (pinfunction "F_7") (pintype "passive"))
    )
    (net (code "167") (name "unconnected-(IC1-NC.1-Pad2)") (class "Default")
      (node (ref "IC1") (pin "2") (pinfunction "NC.1_2") (pintype "bidirectional"))
    )
    (net (code "168") (name "unconnected-(IC1-NC.2-Pad9)") (class "Default")
      (node (ref "IC1") (pin "9") (pinfunction "NC.2_9") (pintype "bidirectional"))
    )
    (net (code "169") (name "unconnected-(IC1-NC.3-Pad12)") (class "Default")
      (node (ref "IC1") (pin "12") (pinfunction "NC.3_12") (pintype "bidirectional"))
    )
    (net (code "170") (name "unconnected-(IC1-NC.4-Pad14)") (class "Default")
      (node (ref "IC1") (pin "14") (pinfunction "NC.4_14") (pintype "bidirectional"))
    )
    (net (code "171") (name "unconnected-(IC1-NC.5-Pad15)") (class "Default")
      (node (ref "IC1") (pin "15") (pinfunction "NC.5_15") (pintype "bidirectional"))
    )
    (net (code "172") (name "unconnected-(IC1-NC.6-Pad16)") (class "Default")
      (node (ref "IC1") (pin "16") (pinfunction "NC.6_16") (pintype "bidirectional"))
    )
    (net (code "173") (name "unconnected-(IC1-{slash}CEO-Pad13)") (class "Default")
      (node (ref "IC1") (pin "13") (pinfunction "/CEO_13") (pintype "bidirectional"))
    )
    (net (code "174") (name "unconnected-(IC3-PC2(AIN2{slash}PCIN11)-Pad5)") (class "Default")
      (node (ref "IC3") (pin "5") (pinfunction "PC2(AIN2/PCIN11)_5") (pintype "bidirectional"))
    )
    (net (code "175") (name "unconnected-(IC3-PC4(PCINT10)-Pad26)") (class "Default")
      (node (ref "IC3") (pin "26") (pinfunction "PC4(PCINT10)_26") (pintype "bidirectional"))
    )
    (net (code "176") (name "unconnected-(IC3-PC5(OC1B{slash}PCINT9)-Pad25)") (class "Default")
      (node (ref "IC3") (pin "25") (pinfunction "PC5(OC1B/PCINT9)_25") (pintype "bidirectional"))
    )
    (net (code "177") (name "unconnected-(IC3-PC6(OC1A{slash}PCINT8)-Pad23)") (class "Default")
      (node (ref "IC3") (pin "23") (pinfunction "PC6(OC1A/PCINT8)_23") (pintype "bidirectional"))
    )
    (net (code "178") (name "unconnected-(IC3-PD0(INT0{slash}OC0B)-Pad6)") (class "Default")
      (node (ref "IC3") (pin "6") (pinfunction "PD0(INT0/OC0B)_6") (pintype "bidirectional"))
    )
    (net (code "179") (name "unconnected-(IC3-PD1(INT1{slash}AIN0)-Pad7)") (class "Default")
      (node (ref "IC3") (pin "7") (pinfunction "PD1(INT1/AIN0)_7") (pintype "bidirectional"))
    )
    (net (code "180") (name "unconnected-(IC3-PD4(INT5{slash}AIN3)-Pad10)") (class "Default")
      (node (ref "IC3") (pin "10") (pinfunction "PD4(INT5/AIN3)_10") (pintype "bidirectional"))
    )
    (net (code "181") (name "unconnected-(IC3-PD5(XCK{slash}AIN4{slash}PCINT12)-Pad11)") (class "Default")
      (node (ref "IC3") (pin "11") (pinfunction "PD5(XCK/AIN4/PCINT12)_11") (pintype "bidirectional"))
    )
    (net (code "182") (name "unconnected-(IC3-PD6(INT6{slash}AIN5{slash}RTS)-Pad12)") (class "Default")
      (node (ref "IC3") (pin "12") (pinfunction "PD6(INT6/AIN5/RTS)_12") (pintype "bidirectional"))
    )
    (net (code "183") (name "unconnected-(IC3-UCAP-Pad27)") (class "Default")
      (node (ref "IC3") (pin "27") (pinfunction "UCAP_27") (pintype "bidirectional"))
    )
    (net (code "184") (name "unconnected-(IC3-XTAL1-Pad1)") (class "Default")
      (node (ref "IC3") (pin "1") (pinfunction "XTAL1_1") (pintype "bidirectional"))
    )
    (net (code "185") (name "unconnected-(IC3-XTAL2{slash}PC0-Pad2)") (class "Default")
      (node (ref "IC3") (pin "2") (pinfunction "XTAL2/PC0_2") (pintype "bidirectional"))
    )
    (net (code "186") (name "unconnected-(IC3-{slash}RESET(PC1)-Pad24)") (class "Default")
      (node (ref "IC3") (pin "24") (pinfunction "/RESET(PC1)_24") (pintype "bidirectional"))
    )
    (net (code "187") (name "unconnected-(J1-Pad2)") (class "Default")
      (node (ref "J1") (pin "2") (pinfunction "2_2") (pintype "passive"))
    )
    (net (code "188") (name "unconnected-(JP1-Pad3)") (class "Default")
      (node (ref "JP1") (pin "3") (pinfunction "3_3") (pintype "passive"))
    )
    (net (code "189") (name "unconnected-(JP1-Pad4)") (class "Default")
      (node (ref "JP1") (pin "4") (pinfunction "4_4") (pintype "passive"))
    )
    (net (code "190") (name "unconnected-(JP1-Pad5)") (class "Default")
      (node (ref "JP1") (pin "5") (pinfunction "5_5") (pintype "passive"))
    )
    (net (code "191") (name "unconnected-(JP1-Pad6)") (class "Default")
      (node (ref "JP1") (pin "6") (pinfunction "6_6") (pintype "passive"))
    )
    (net (code "192") (name "unconnected-(JP1-Pad7)") (class "Default")
      (node (ref "JP1") (pin "7") (pinfunction "7_7") (pintype "passive"))
    )
    (net (code "193") (name "unconnected-(JP1-Pad8)") (class "Default")
      (node (ref "JP1") (pin "8") (pinfunction "8_8") (pintype "passive"))
    )
    (net (code "194") (name "unconnected-(JP1-Pad9)") (class "Default")
      (node (ref "JP1") (pin "9") (pinfunction "9_9") (pintype "passive"))
    )
    (net (code "195") (name "unconnected-(JP1-Pad10)") (class "Default")
      (node (ref "JP1") (pin "10") (pinfunction "10_10") (pintype "passive"))
    )
    (net (code "196") (name "unconnected-(JP1-Pad11)") (class "Default")
      (node (ref "JP1") (pin "11") (pinfunction "11_11") (pintype "passive"))
    )
    (net (code "197") (name "unconnected-(JP1-Pad12)") (class "Default")
      (node (ref "JP1") (pin "12") (pinfunction "12_12") (pintype "passive"))
    )
    (net (code "198") (name "unconnected-(JP1-Pad13)") (class "Default")
      (node (ref "JP1") (pin "13") (pinfunction "13_13") (pintype "passive"))
    )
    (net (code "199") (name "unconnected-(JP1-Pad14)") (class "Default")
      (node (ref "JP1") (pin "14") (pinfunction "14_14") (pintype "passive"))
    )
    (net (code "200") (name "unconnected-(JP1-Pad15)") (class "Default")
      (node (ref "JP1") (pin "15") (pinfunction "15_15") (pintype "passive"))
    )
    (net (code "201") (name "unconnected-(JP1-Pad16)") (class "Default")
      (node (ref "JP1") (pin "16") (pinfunction "16_16") (pintype "passive"))
    )
    (net (code "202") (name "unconnected-(JP1-Pad17)") (class "Default")
      (node (ref "JP1") (pin "17") (pinfunction "17_17") (pintype "passive"))
    )
    (net (code "203") (name "unconnected-(JP1-Pad18)") (class "Default")
      (node (ref "JP1") (pin "18") (pinfunction "18_18") (pintype "passive"))
    )
    (net (code "204") (name "unconnected-(JP1-Pad19)") (class "Default")
      (node (ref "JP1") (pin "19") (pinfunction "19_19") (pintype "passive"))
    )
    (net (code "205") (name "unconnected-(JP1-Pad20)") (class "Default")
      (node (ref "JP1") (pin "20") (pinfunction "20_20") (pintype "passive"))
    )
    (net (code "206") (name "unconnected-(JP2-Pad1)") (class "Default")
      (node (ref "JP2") (pin "1") (pinfunction "1_1") (pintype "passive"))
    )
    (net (code "207") (name "unconnected-(JP2-Pad2)") (class "Default")
      (node (ref "JP2") (pin "2") (pinfunction "2_2") (pintype "passive"))
    )
    (net (code "208") (name "unconnected-(JP2-Pad3)") (class "Default")
      (node (ref "JP2") (pin "3") (pinfunction "3_3") (pintype "passive"))
    )
    (net (code "209") (name "unconnected-(JP2-Pad4)") (class "Default")
      (node (ref "JP2") (pin "4") (pinfunction "4_4") (pintype "passive"))
    )
    (net (code "210") (name "unconnected-(JP2-Pad5)") (class "Default")
      (node (ref "JP2") (pin "5") (pinfunction "5_5") (pintype "passive"))
    )
    (net (code "211") (name "unconnected-(JP2-Pad6)") (class "Default")
      (node (ref "JP2") (pin "6") (pinfunction "6_6") (pintype "passive"))
    )
    (net (code "212") (name "unconnected-(JP2-Pad7)") (class "Default")
      (node (ref "JP2") (pin "7") (pinfunction "7_7") (pintype "passive"))
    )
    (net (code "213") (name "unconnected-(JP2-Pad8)") (class "Default")
      (node (ref "JP2") (pin "8") (pinfunction "8_8") (pintype "passive"))
    )
    (net (code "214") (name "unconnected-(JP2-Pad9)") (class "Default")
      (node (ref "JP2") (pin "9") (pinfunction "9_9") (pintype "passive"))
    )
    (net (code "215") (name "unconnected-(JP2-Pad10)") (class "Default")
      (node (ref "JP2") (pin "10") (pinfunction "10_10") (pintype "passive"))
    )
    (net (code "216") (name "unconnected-(JP2-Pad11)") (class "Default")
      (node (ref "JP2") (pin "11") (pinfunction "11_11") (pintype "passive"))
    )
    (net (code "217") (name "unconnected-(JP2-Pad12)") (class "Default")
      (node (ref "JP2") (pin "12") (pinfunction "12_12") (pintype "passive"))
    )
    (net (code "218") (name "unconnected-(JP2-Pad13)") (class "Default")
      (node (ref "JP2") (pin "13") (pinfunction "13_13") (pintype "passive"))
    )
    (net (code "219") (name "unconnected-(JP2-Pad14)") (class "Default")
      (node (ref "JP2") (pin "14") (pinfunction "14_14") (pintype "passive"))
    )
    (net (code "220") (name "unconnected-(JP2-Pad15)") (class "Default")
      (node (ref "JP2") (pin "15") (pinfunction "15_15") (pintype "passive"))
    )
    (net (code "221") (name "unconnected-(JP2-Pad16)") (class "Default")
      (node (ref "JP2") (pin "16") (pinfunction "16_16") (pintype "passive"))
    )
    (net (code "222") (name "unconnected-(JP2-Pad17)") (class "Default")
      (node (ref "JP2") (pin "17") (pinfunction "17_17") (pintype "passive"))
    )
    (net (code "223") (name "unconnected-(JP2-Pad18)") (class "Default")
      (node (ref "JP2") (pin "18") (pinfunction "18_18") (pintype "passive"))
    )
    (net (code "224") (name "unconnected-(JP2-Pad19)") (class "Default")
      (node (ref "JP2") (pin "19") (pinfunction "19_19") (pintype "passive"))
    )
    (net (code "225") (name "unconnected-(JP2-Pad20)") (class "Default")
      (node (ref "JP2") (pin "20") (pinfunction "20_20") (pintype "passive"))
    )
    (net (code "226") (name "unconnected-(REG1.2-VOUT2-Pad2)") (class "Default")
      (node (ref "REG1.2") (pin "2") (pinfunction "VOUT2_2") (pintype "bidirectional"))
    )
    (net (code "227") (name "unconnected-(REG2.5-VOUT2-Pad2)") (class "Default")
      (node (ref "REG2.5") (pin "2") (pinfunction "VOUT2_2") (pintype "bidirectional"))
    )
    (net (code "228") (name "unconnected-(U$2-TRI-PadENA)") (class "Default")
      (node (ref "U$2") (pin "ENA") (pinfunction "TRI_ENA") (pintype "input"))
    )
    (net (code "229") (name "unconnected-(U$3-Pad1)") (class "Default")
      (node (ref "U$3") (pin "1") (pinfunction "1_1") (pintype "passive"))
    )
    (net (code "230") (name "unconnected-(U$3-Pad2)") (class "Default")
      (node (ref "U$3") (pin "2") (pinfunction "2_2") (pintype "passive"))
    )
    (net (code "231") (name "unconnected-(U$3-Pad3)") (class "Default")
      (node (ref "U$3") (pin "3") (pinfunction "3_3") (pintype "passive"))
    )
    (net (code "232") (name "unconnected-(U$3-Pad4)") (class "Default")
      (node (ref "U$3") (pin "4") (pinfunction "4_4") (pintype "passive"))
    )
    (net (code "233") (name "unconnected-(U$3-Pad5)") (class "Default")
      (node (ref "U$3") (pin "5") (pinfunction "5_5") (pintype "passive"))
    )
    (net (code "234") (name "unconnected-(U$3-Pad6)") (class "Default")
      (node (ref "U$3") (pin "6") (pinfunction "6_6") (pintype "passive"))
    )
    (net (code "235") (name "unconnected-(U$3-Pad7)") (class "Default")
      (node (ref "U$3") (pin "7") (pinfunction "7_7") (pintype "passive"))
    )
    (net (code "236") (name "unconnected-(U$3-Pad8)") (class "Default")
      (node (ref "U$3") (pin "8") (pinfunction "8_8") (pintype "passive"))
    )
    (net (code "237") (name "unconnected-(U$3-Pad9)") (class "Default")
      (node (ref "U$3") (pin "9") (pinfunction "9_9") (pintype "passive"))
    )
    (net (code "238") (name "unconnected-(U$3-Pad10)") (class "Default")
      (node (ref "U$3") (pin "10") (pinfunction "10_10") (pintype "passive"))
    )
    (net (code "239") (name "unconnected-(U$4-VOUT2-Pad2)") (class "Default")
      (node (ref "U$4") (pin "2") (pinfunction "VOUT2_2") (pintype "bidirectional"))
    )
    (net (code "240") (name "unconnected-(U1A-IO_L27P_0-PadP135)") (class "Default")
      (node (ref "U1") (pin "P135") (pinfunction "IO_L27P_0_P135") (pintype "bidirectional"))
    )
    (net (code "241") (name "unconnected-(U1A-IO_L30N_0-PadP132)") (class "Default")
      (node (ref "U1") (pin "P132") (pinfunction "IO_L30N_0_P132") (pintype "bidirectional"))
    )
    (net (code "242") (name "unconnected-(U1A-IO_L30P_0-PadP131)") (class "Default")
      (node (ref "U1") (pin "P131") (pinfunction "IO_L30P_0_P131") (pintype "bidirectional"))
    )
    (net (code "243") (name "unconnected-(U1A-IO_L31N_0-PadP130)") (class "Default")
      (node (ref "U1") (pin "P130") (pinfunction "IO_L31N_0_P130") (pintype "bidirectional"))
    )
    (net (code "244") (name "unconnected-(U1A-IO_L31P_0VREF_0-PadP129)") (class "Default")
      (node (ref "U1") (pin "P129") (pinfunction "IO_L31P_0VREF_0_P129") (pintype "bidirectional"))
    )
    (net (code "245") (name "unconnected-(U1A-IO_L32N_0GCLK7-PadP128)") (class "Default")
      (node (ref "U1") (pin "P128") (pinfunction "IO_L32N_0GCLK7_P128") (pintype "bidirectional"))
    )
    (net (code "246") (name "unconnected-(U1A-IO_L32P_0GCLK6-PadP127)") (class "Default")
      (node (ref "U1") (pin "P127") (pinfunction "IO_L32P_0GCLK6_P127") (pintype "bidirectional"))
    )
    (net (code "247") (name "unconnected-(U1C-IO-PadP116)") (class "Default")
      (node (ref "U1") (pin "P116") (pinfunction "IO_P116") (pintype "bidirectional"))
    )
    (net (code "248") (name "unconnected-(U1C-IO_L01N_1VRP_1-PadP113)") (class "Default")
      (node (ref "U1") (pin "P113") (pinfunction "IO_L01N_1VRP_1_P113") (pintype "bidirectional"))
    )
    (net (code "249") (name "unconnected-(U1C-IO_L01P_1VRN_1-PadP112)") (class "Default")
      (node (ref "U1") (pin "P112") (pinfunction "IO_L01P_1VRN_1_P112") (pintype "bidirectional"))
    )
    (net (code "250") (name "unconnected-(U1C-IO_L28N_1-PadP119)") (class "Default")
      (node (ref "U1") (pin "P119") (pinfunction "IO_L28N_1_P119") (pintype "bidirectional"))
    )
    (net (code "251") (name "unconnected-(U1C-IO_L28P_1-PadP118)") (class "Default")
      (node (ref "U1") (pin "P118") (pinfunction "IO_L28P_1_P118") (pintype "bidirectional"))
    )
    (net (code "252") (name "unconnected-(U1C-IO_L31N_1VREF_1-PadP123)") (class "Default")
      (node (ref "U1") (pin "P123") (pinfunction "IO_L31N_1VREF_1_P123") (pintype "bidirectional"))
    )
    (net (code "253") (name "unconnected-(U1C-IO_L31P_1-PadP122)") (class "Default")
      (node (ref "U1") (pin "P122") (pinfunction "IO_L31P_1_P122") (pintype "bidirectional"))
    )
    (net (code "254") (name "unconnected-(U1C-IO_L32N_1GCLK5-PadP125)") (class "Default")
      (node (ref "U1") (pin "P125") (pinfunction "IO_L32N_1GCLK5_P125") (pintype "bidirectional"))
    )
    (net (code "255") (name "unconnected-(U1C-IO_L32P_1GCLK4-PadP124)") (class "Default")
      (node (ref "U1") (pin "P124") (pinfunction "IO_L32P_1GCLK4_P124") (pintype "bidirectional"))
    )
    (net (code "256") (name "unconnected-(U1N-HSWAP_EN-PadP142)") (class "Default")
      (node (ref "U1") (pin "P142") (pinfunction "HSWAP_EN_P142") (pintype "bidirectional"))
    )
    (net (code "257") (name "unconnected-(X1-3-Pad2)") (class "Default")
      (node (ref "X1") (pin "2") (pinfunction "3_2") (pintype "passive"))
    )
    (net (code "258") (name "unconnected-(X2-Pad10)") (class "Default")
      (node (ref "X2") (pin "10") (pinfunction "10_10") (pintype "passive"))
    )
    (net (code "259") (name "unconnected-(X2-Pad12)") (class "Default")
      (node (ref "X2") (pin "12") (pinfunction "12_12") (pintype "passive"))
    )
    (net (code "260") (name "unconnected-(X3-Pad2)") (class "Default")
      (node (ref "X3") (pin "2") (pinfunction "2_2") (pintype "passive"))
    )
    (net (code "261") (name "unconnected-(X3-Pad8)") (class "Default")
      (node (ref "X3") (pin "8") (pinfunction "8_8") (pintype "passive"))
    )
    (net (code "262") (name "unconnected-(X4-PadG2)") (class "Default")
      (node (ref "X4") (pin "G2") (pinfunction "G2_G2") (pintype "passive"))
    )
    (net (code "263") (name "unconnected-(X5-PadG2)") (class "Default")
      (node (ref "X5") (pin "G2") (pinfunction "G2_G2") (pintype "passive"))
    )
    (net (code "264") (name "unconnected-(X6-Pad1)") (class "Default")
      (node (ref "X6") (pin "1") (pinfunction "1_1") (pintype "passive"))
    )
  )
)
